# dsy01.net
KiCad netlist of a schematic drawn in EAGLE
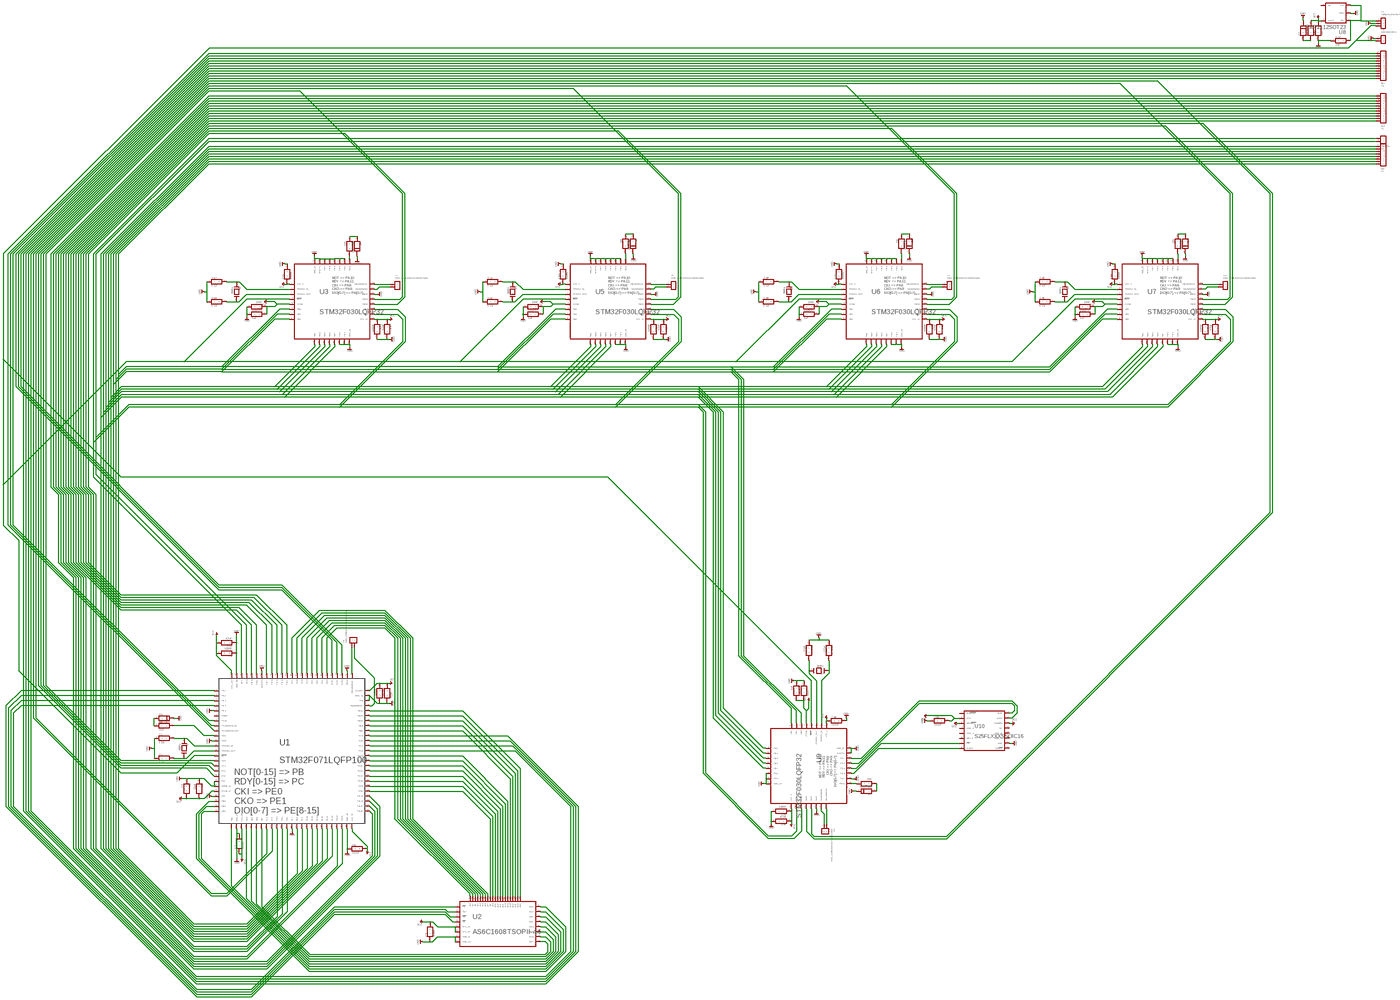
[diagram p0: schematic, sheet 1, overview]
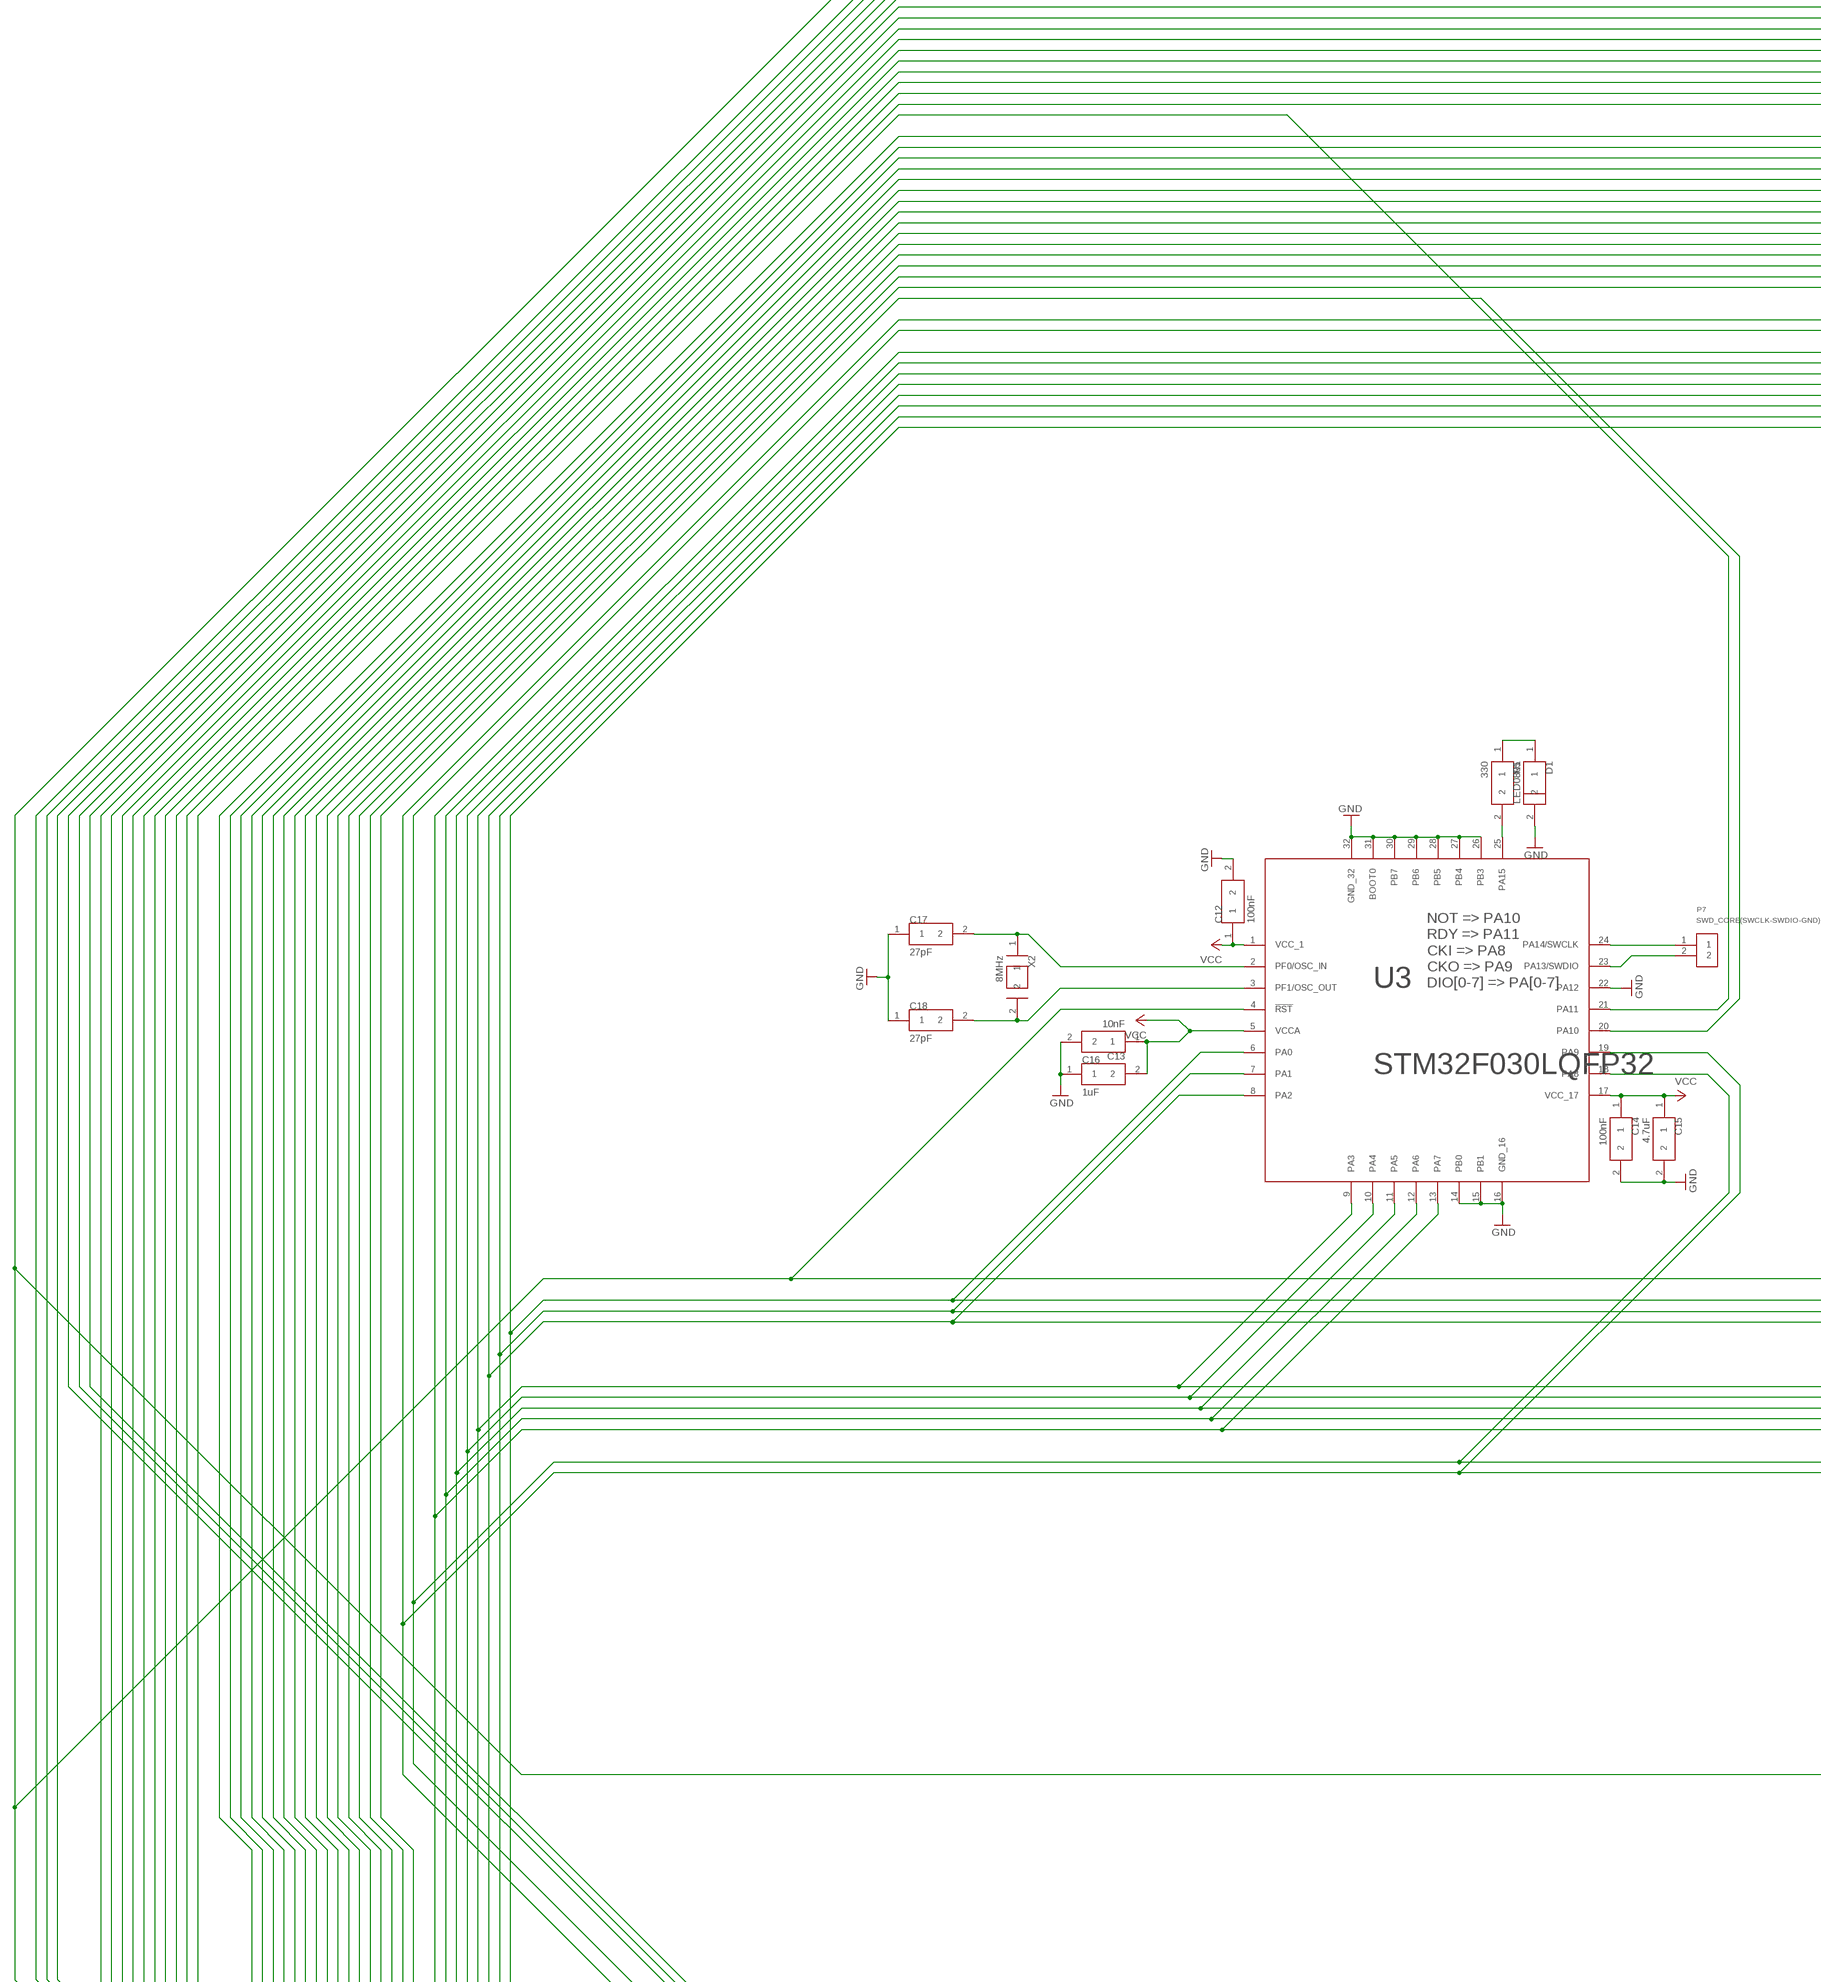
[diagram p1: schematic, sheet 1, part 1 of 7]
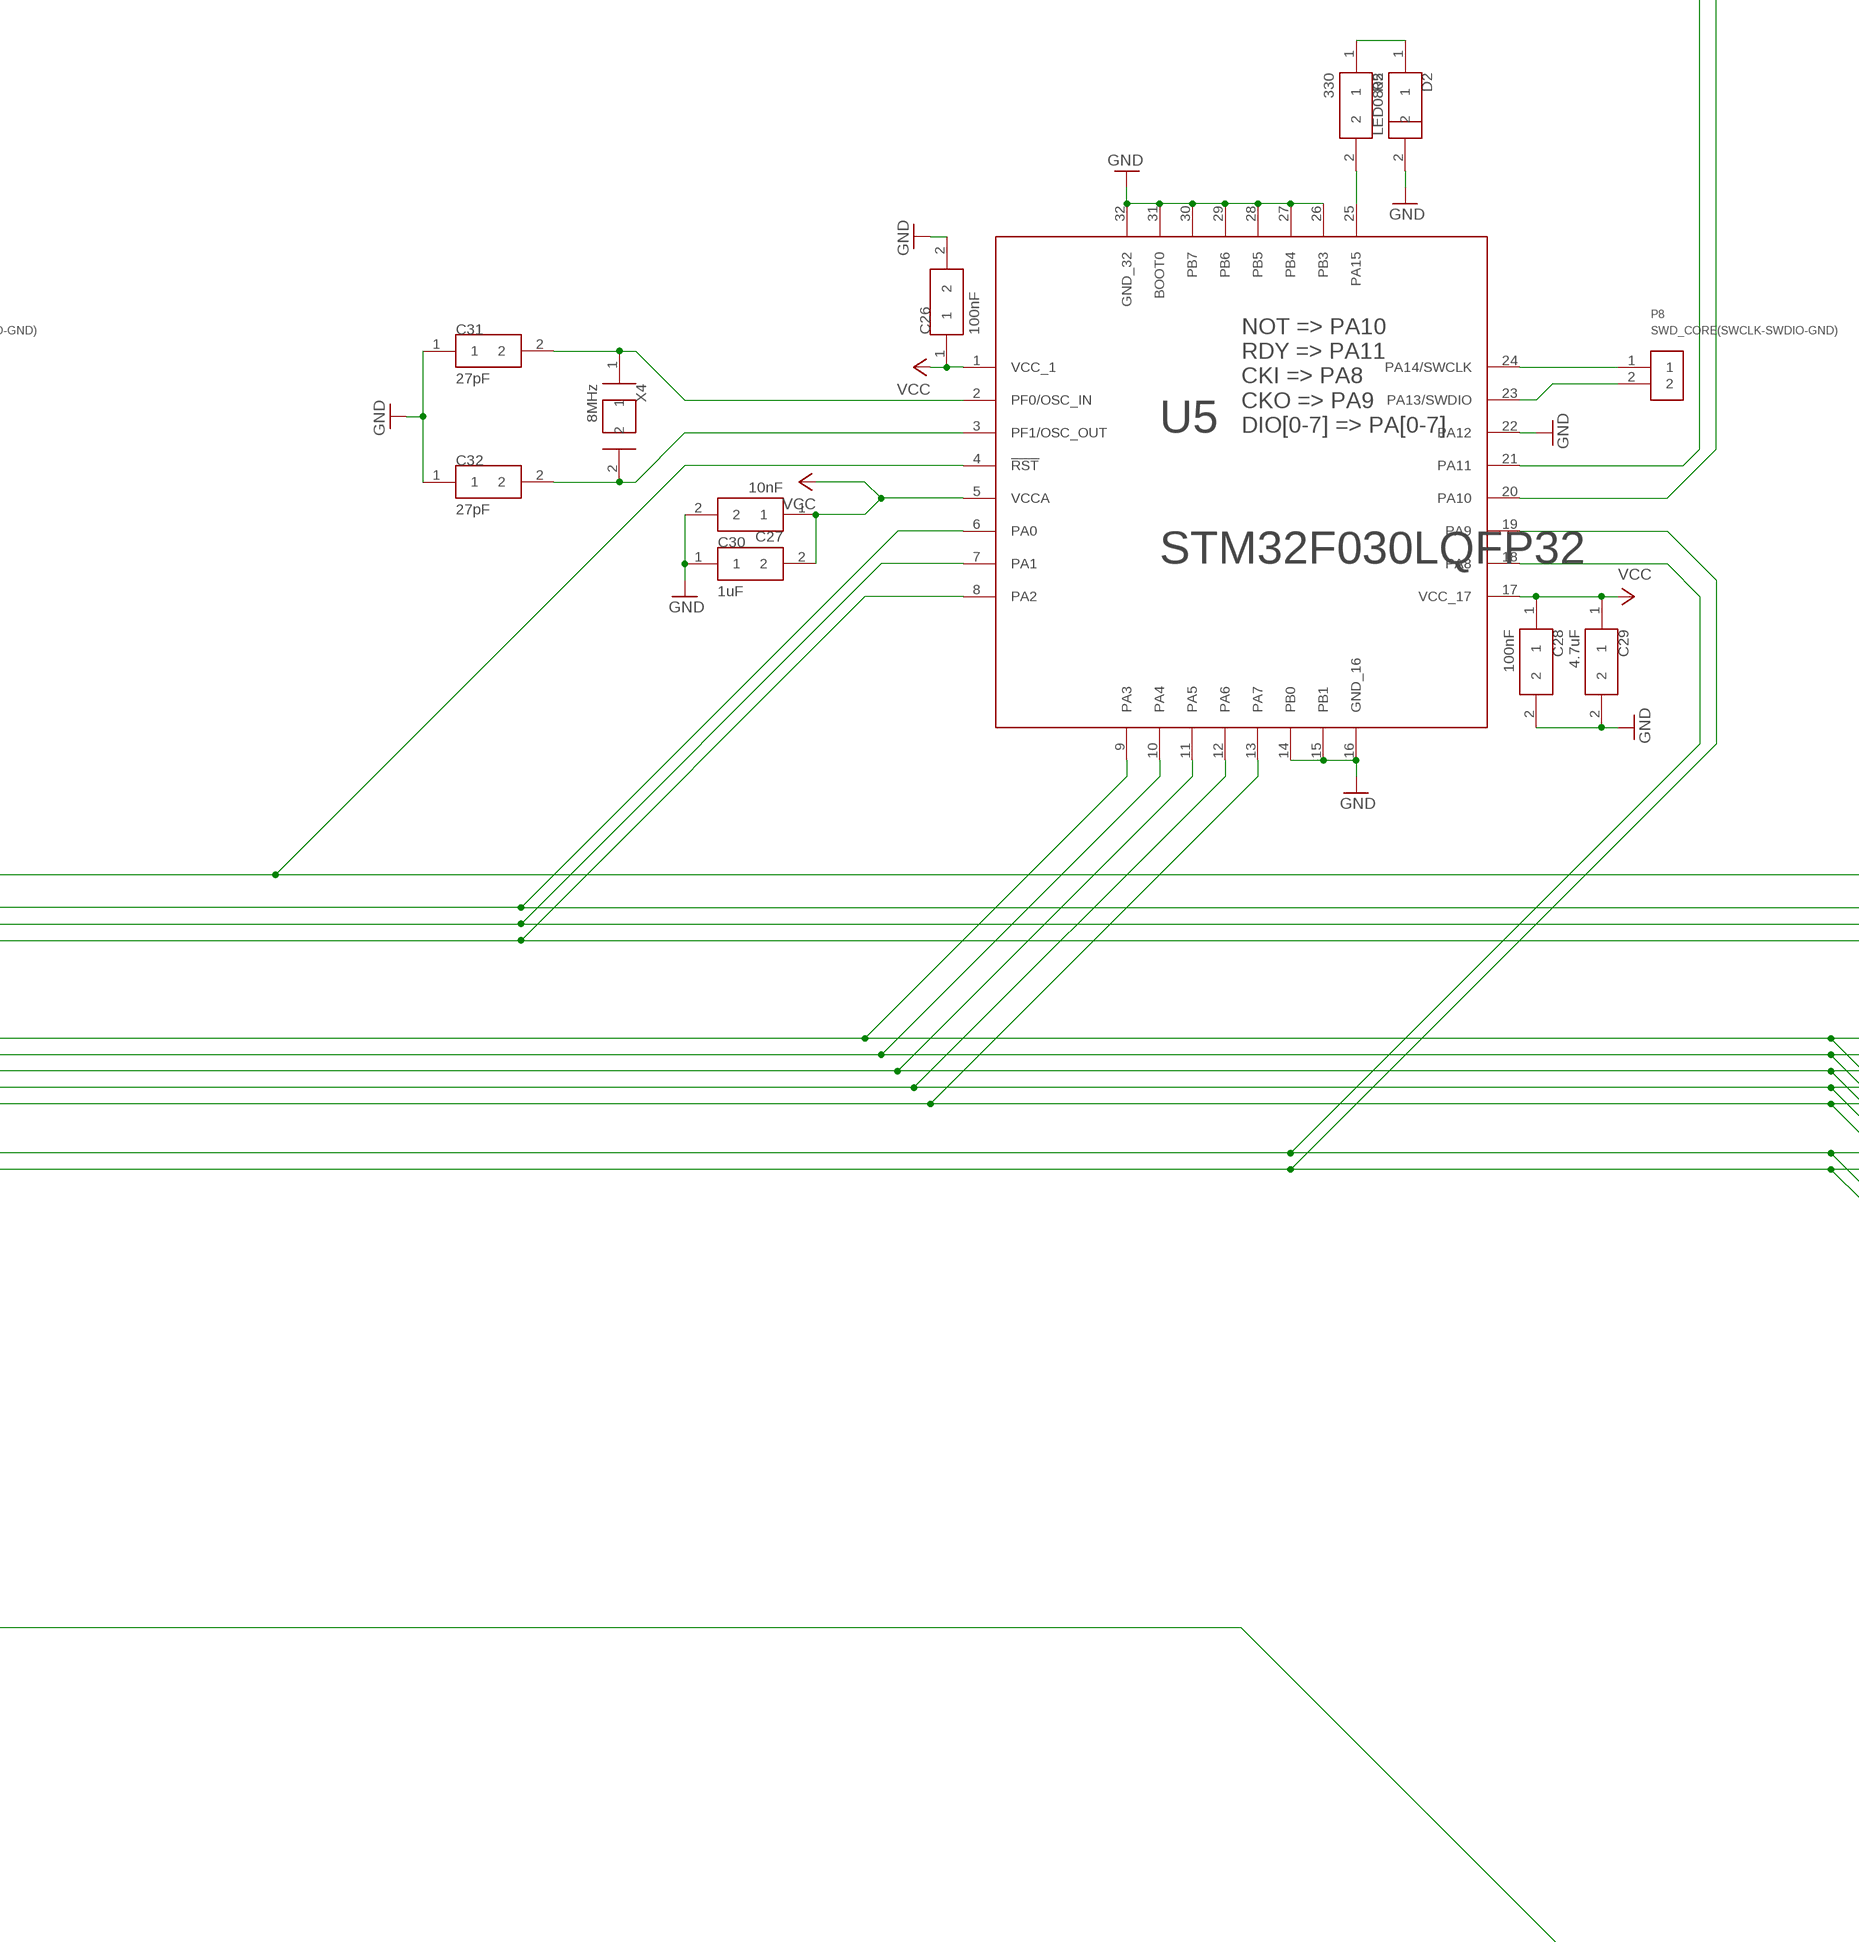
[diagram p2: schematic, sheet 1, part 2 of 7]
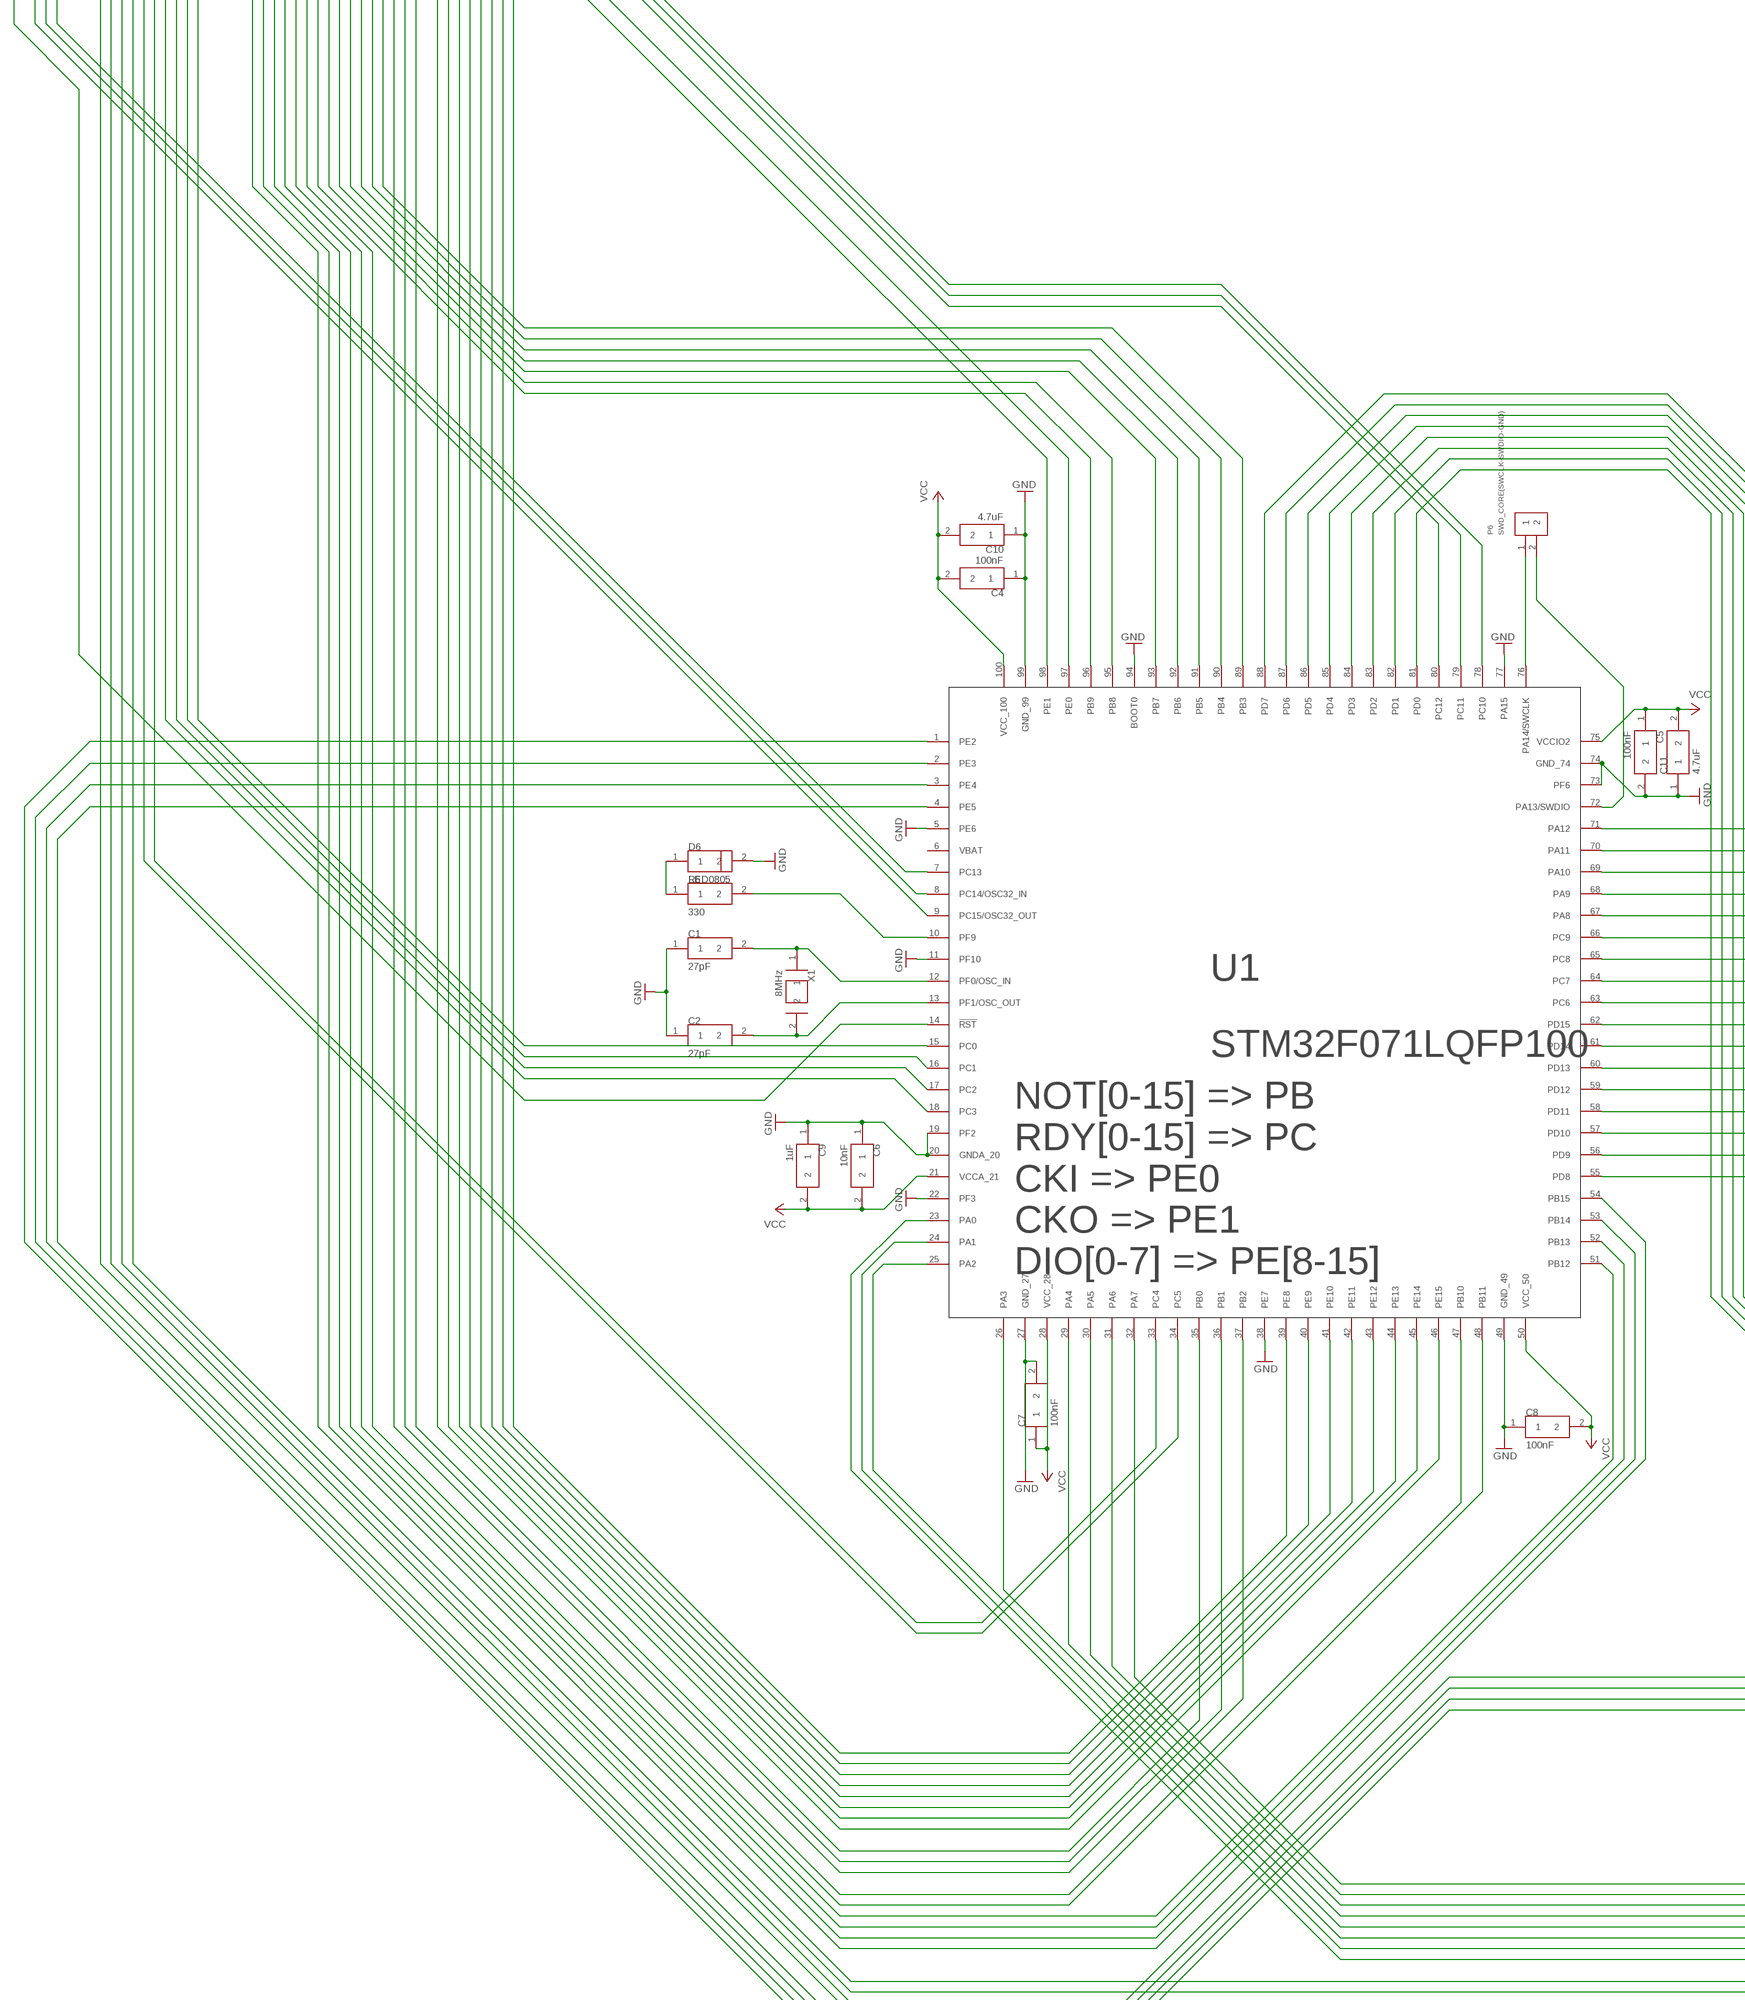
[diagram p3: schematic, sheet 1, part 3 of 7]
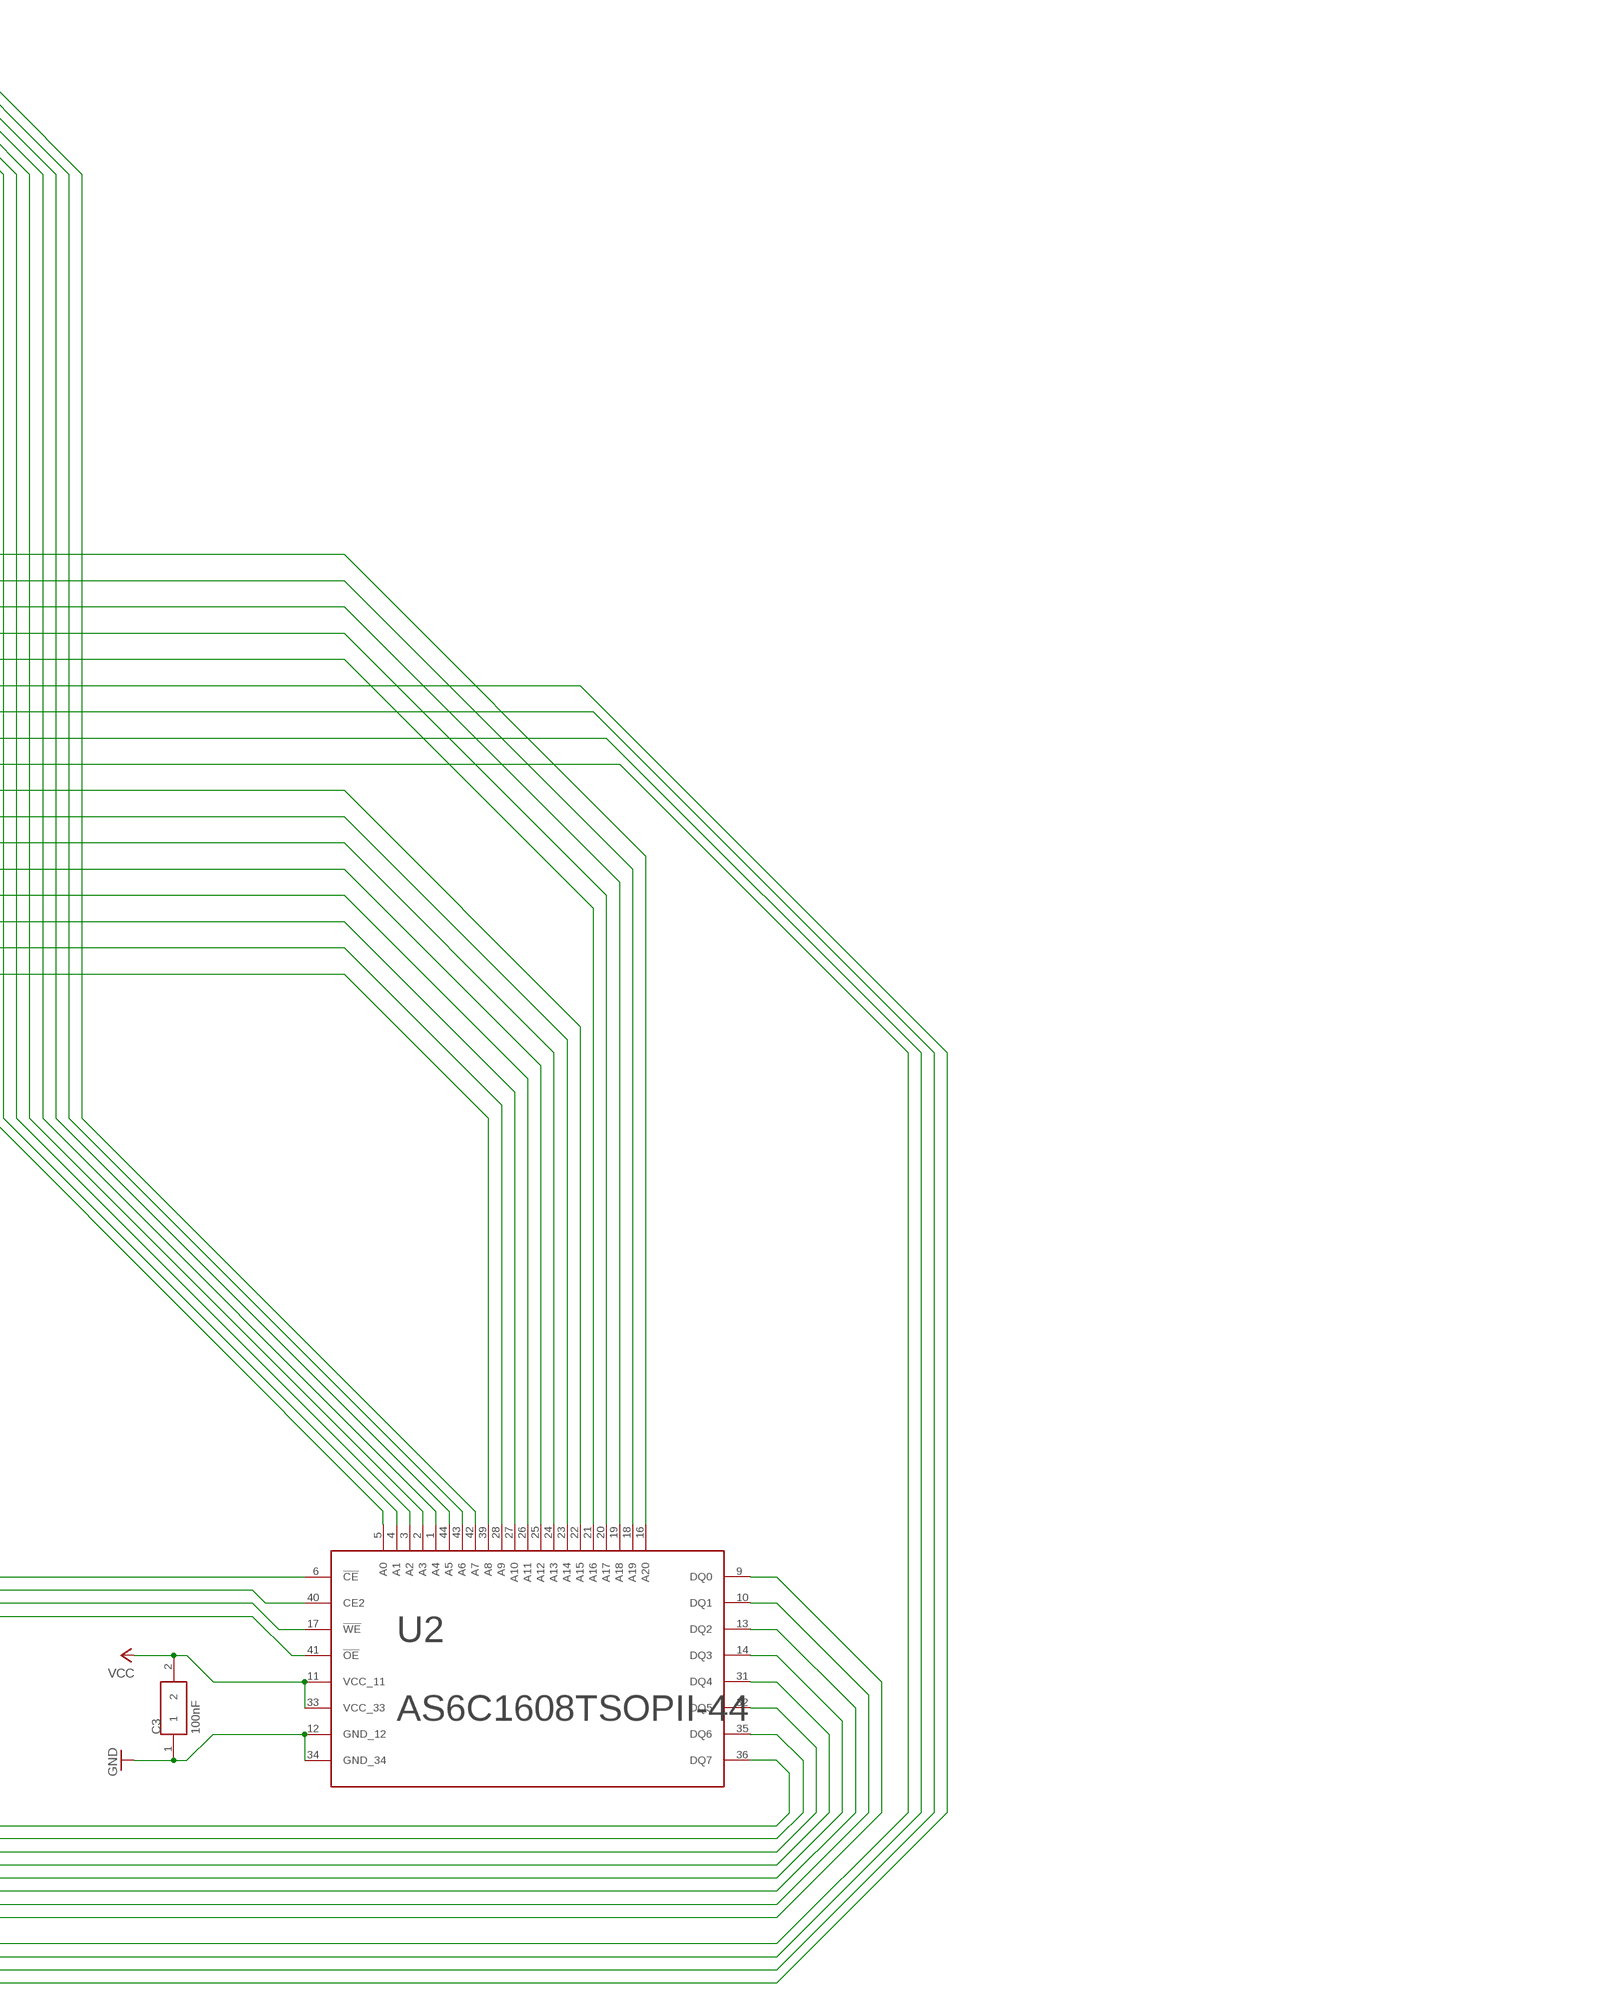
[diagram p4: schematic, sheet 1, part 4 of 7]
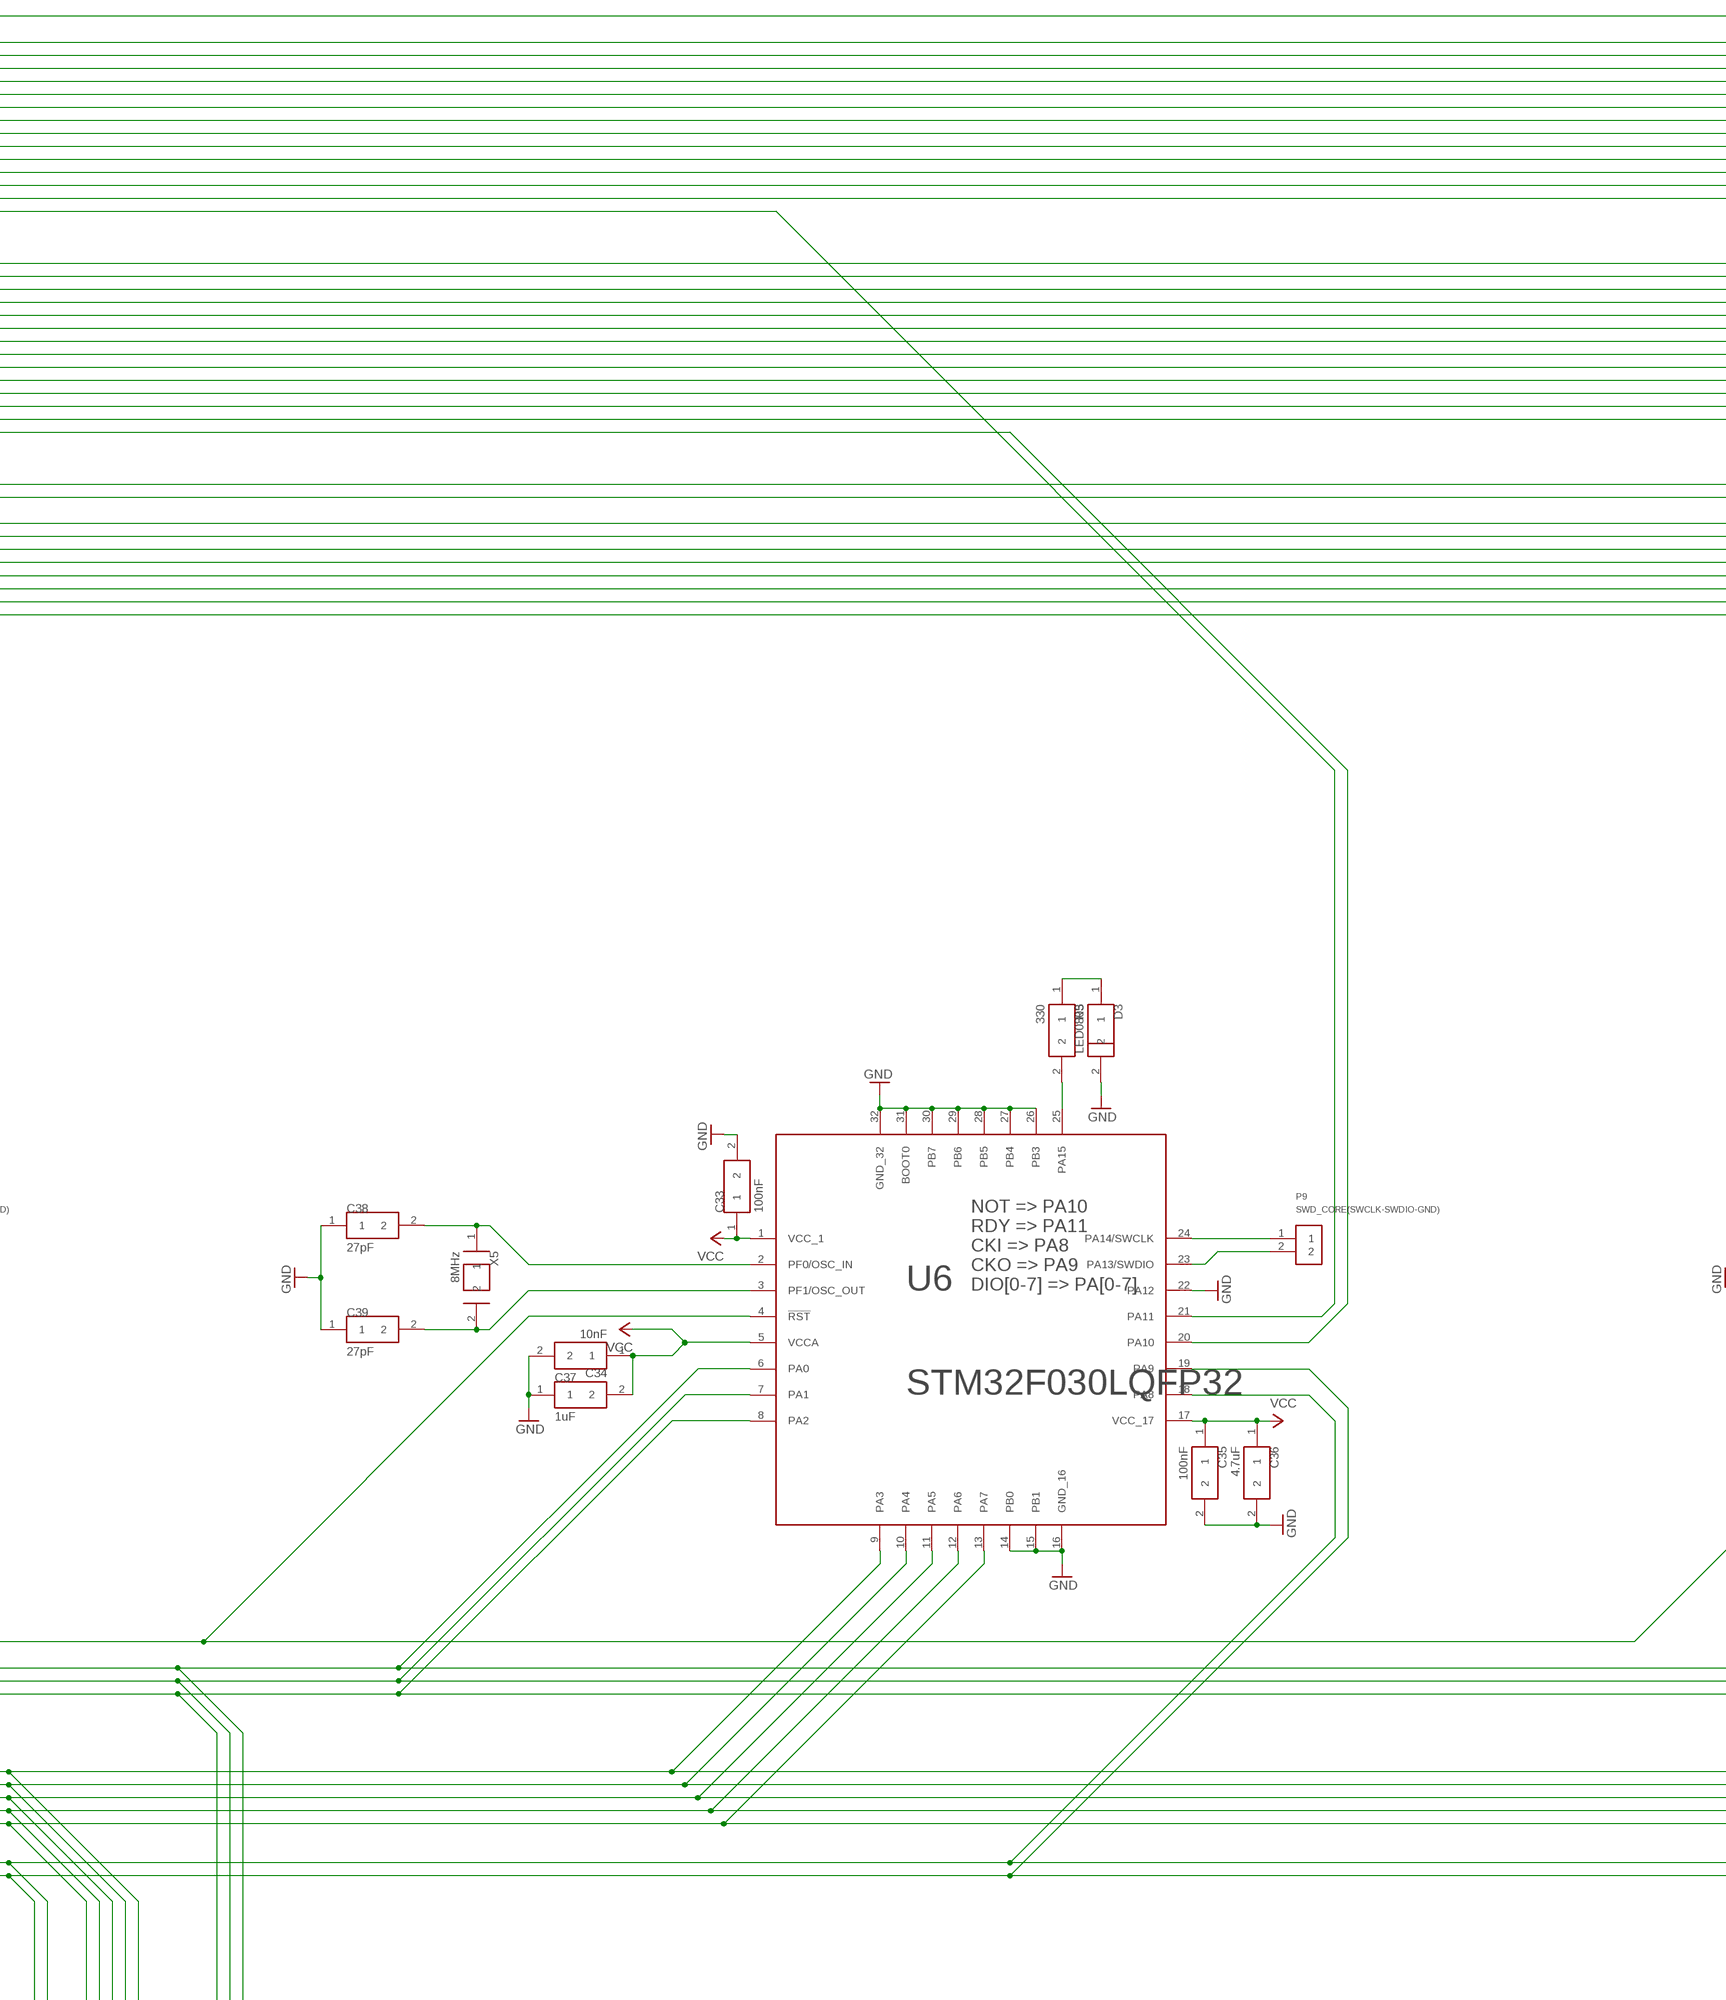
[diagram p5: schematic, sheet 1, part 5 of 7]
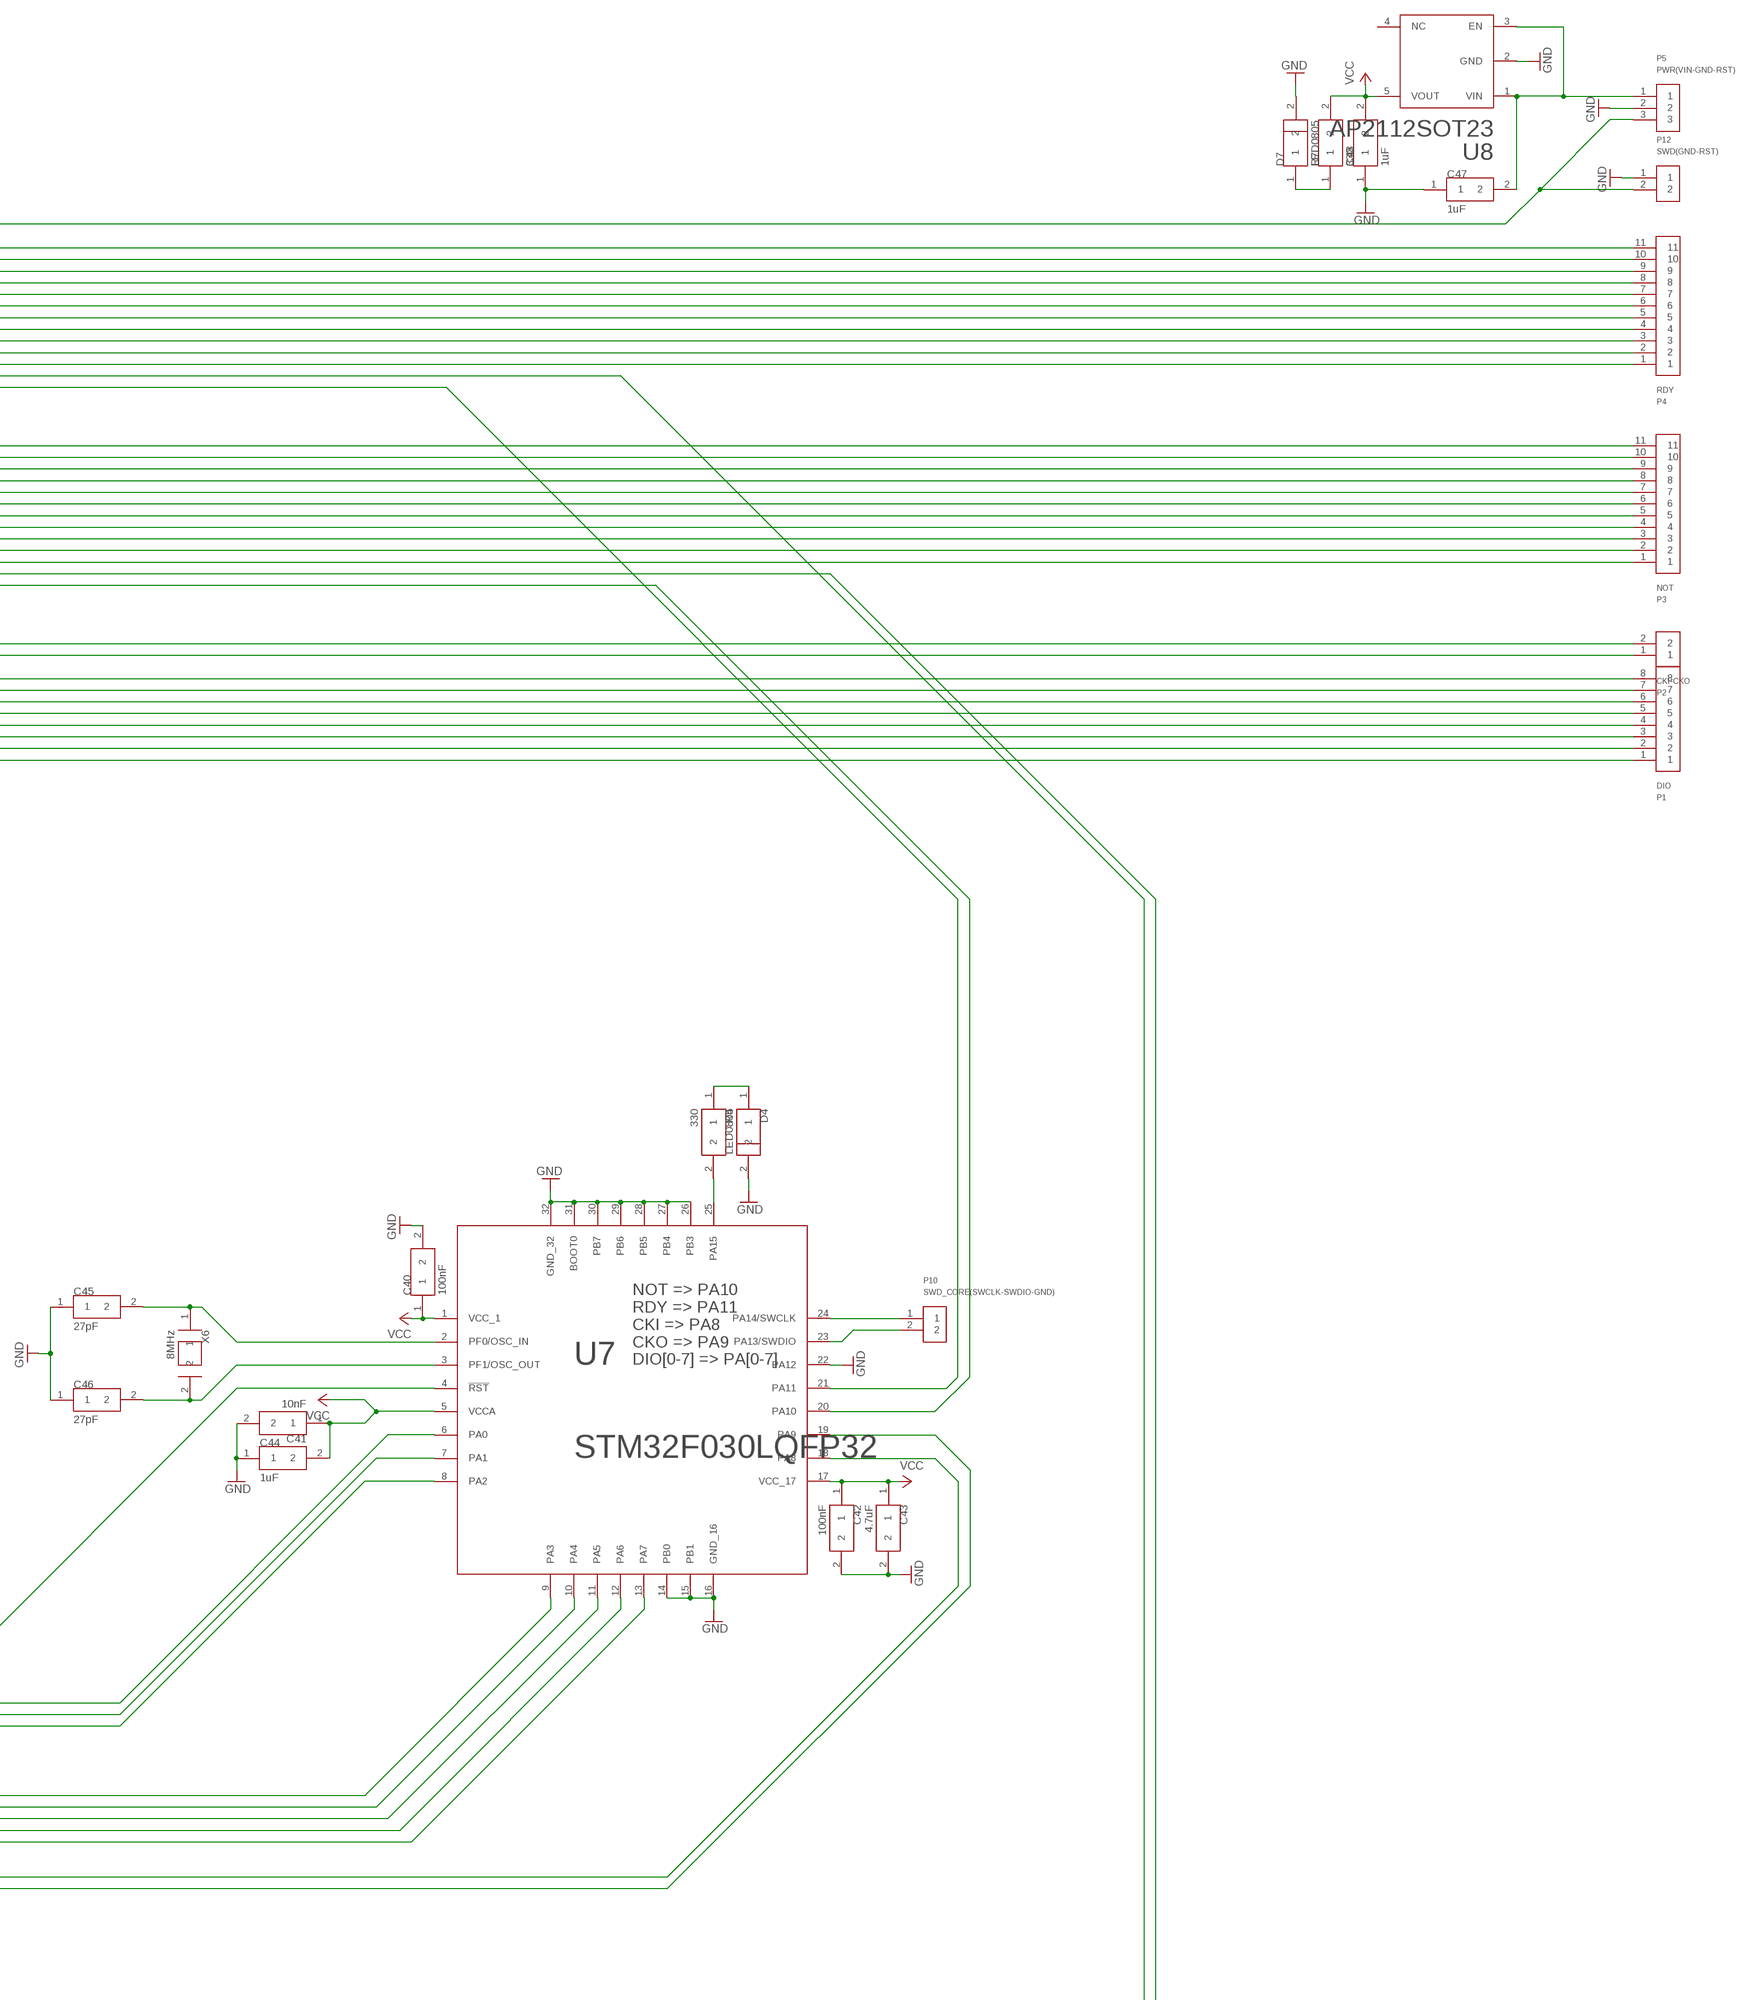
[diagram p6: schematic, sheet 1, part 6 of 7]
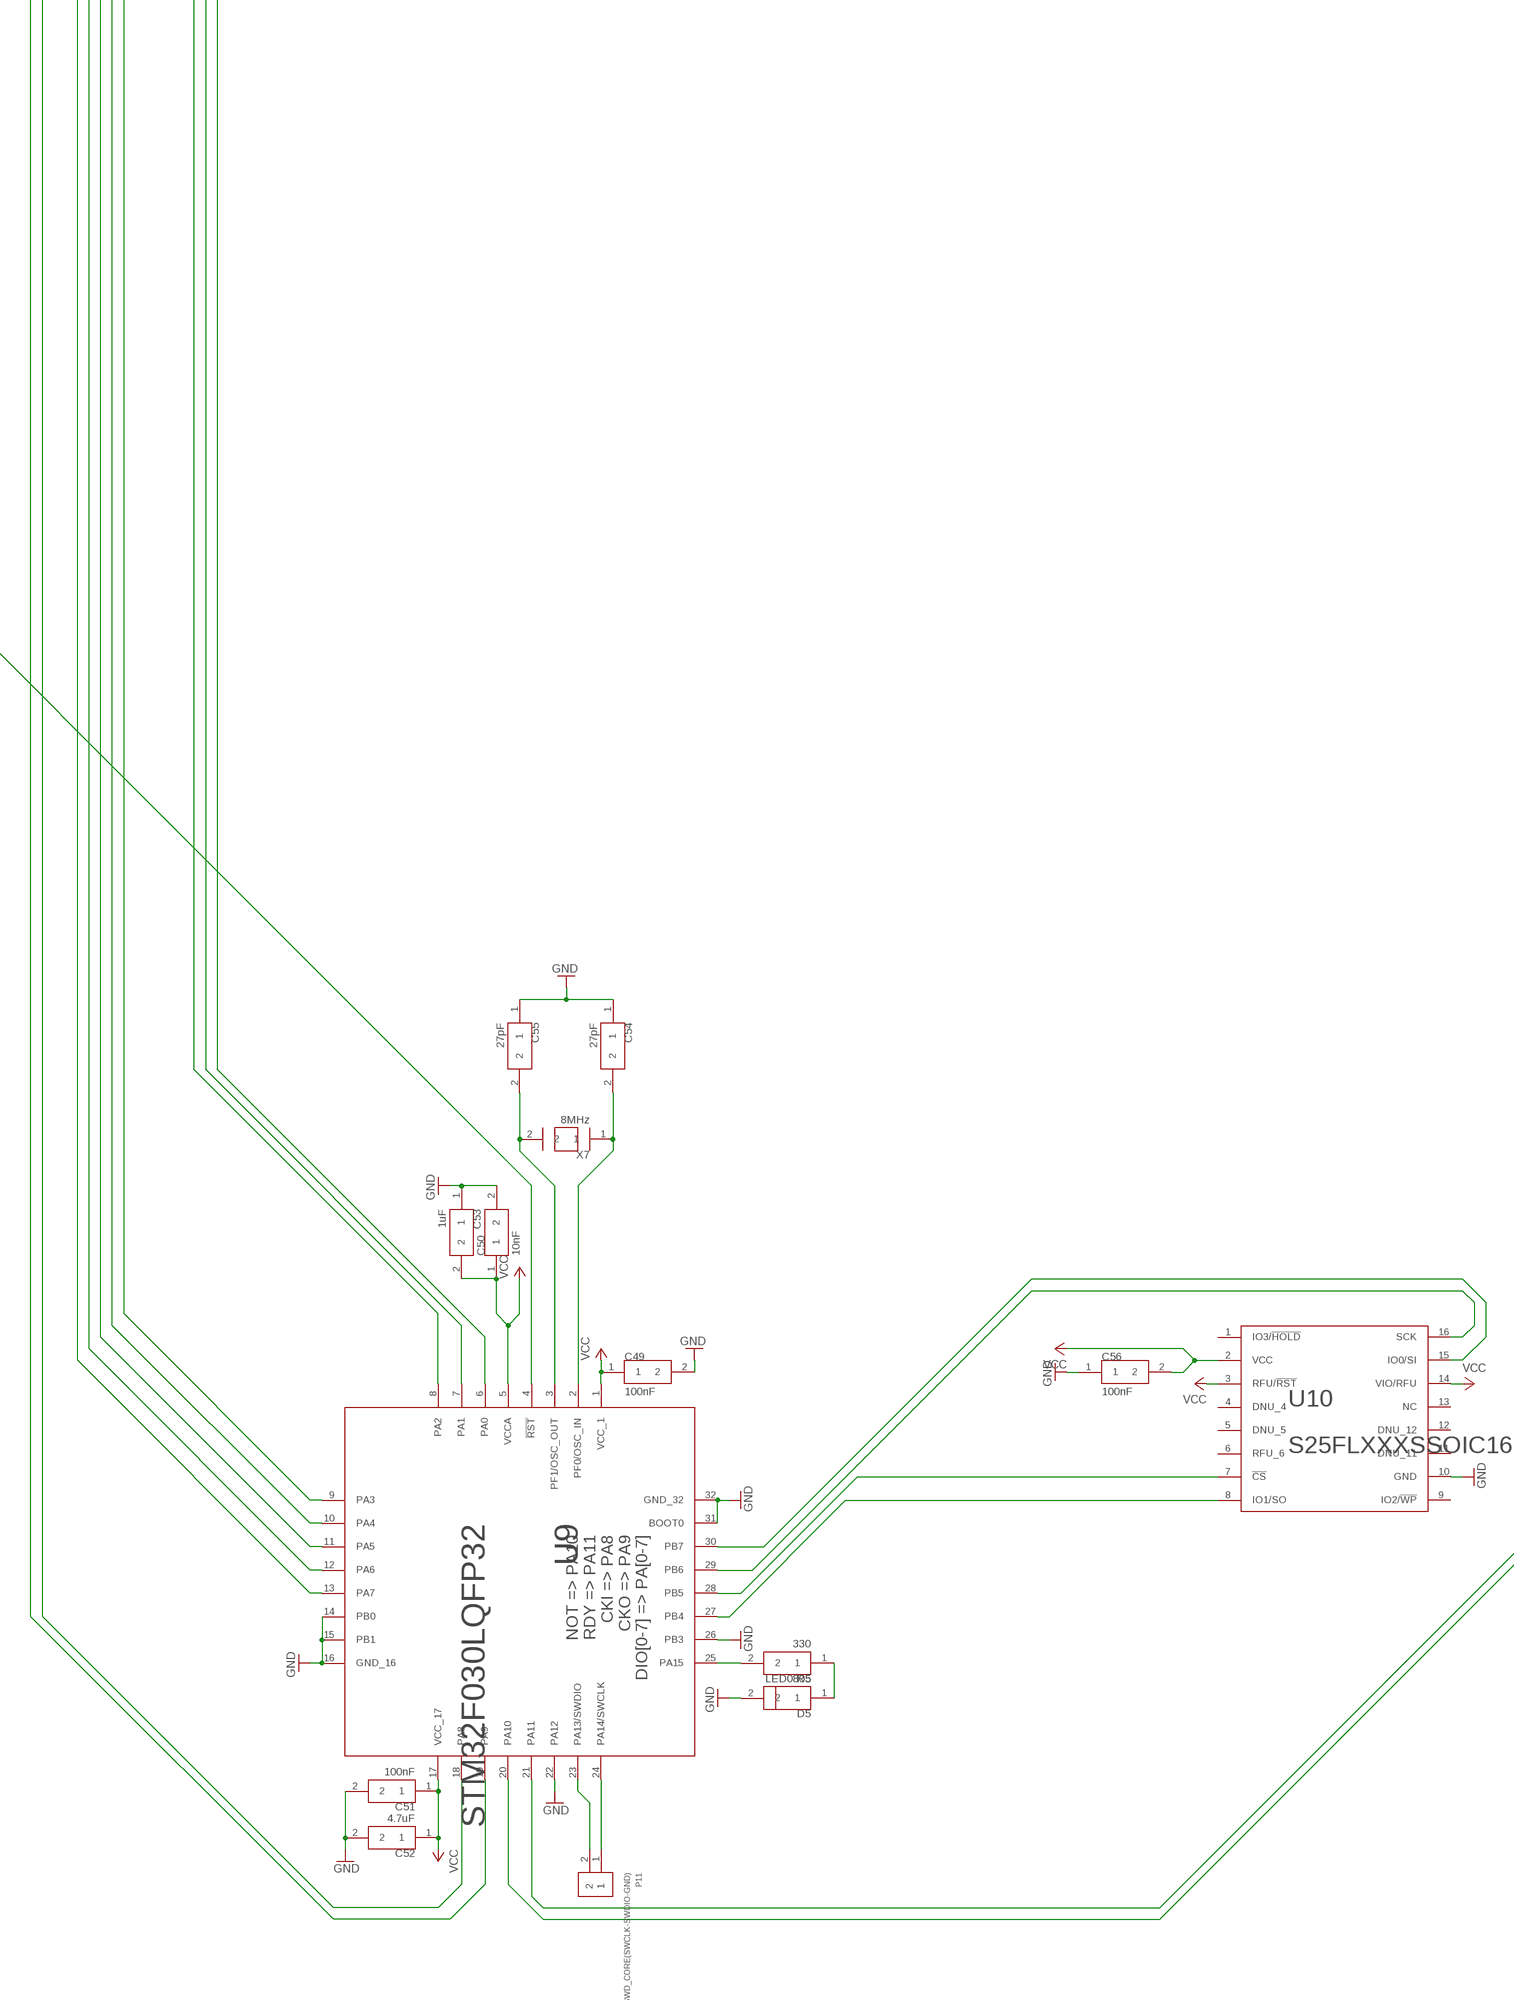
[diagram p7: schematic, sheet 1, part 7 of 7]

(export (version "E")
  (design (tool "Eeschema 10.0.6"))
  (components
    (comp (ref "C1")
      (value "27pF")
      (footprint "eagle-import:0805")
      (libsource (lib "eagle-import") (part "CAP0805"))
    )
    (comp (ref "C2")
      (value "27pF")
      (footprint "eagle-import:0805")
      (libsource (lib "eagle-import") (part "CAP0805"))
    )
    (comp (ref "C3")
      (value "100nF")
      (footprint "eagle-import:0805")
      (libsource (lib "eagle-import") (part "CAP0805"))
    )
    (comp (ref "C4")
      (value "100nF")
      (footprint "eagle-import:0805")
      (libsource (lib "eagle-import") (part "CAP0805"))
    )
    (comp (ref "C5")
      (value "100nF")
      (footprint "eagle-import:0805")
      (libsource (lib "eagle-import") (part "CAP0805"))
    )
    (comp (ref "C6")
      (value "10nF")
      (footprint "eagle-import:0805")
      (libsource (lib "eagle-import") (part "CAP0805"))
    )
    (comp (ref "C7")
      (value "100nF")
      (footprint "eagle-import:0805")
      (libsource (lib "eagle-import") (part "CAP0805"))
    )
    (comp (ref "C8")
      (value "100nF")
      (footprint "eagle-import:0805")
      (libsource (lib "eagle-import") (part "CAP0805"))
    )
    (comp (ref "C9")
      (value "1uF")
      (footprint "eagle-import:0805")
      (libsource (lib "eagle-import") (part "CAP0805"))
    )
    (comp (ref "C10")
      (value "4.7uF")
      (footprint "eagle-import:0805")
      (libsource (lib "eagle-import") (part "CAP0805"))
    )
    (comp (ref "C11")
      (value "4.7uF")
      (footprint "eagle-import:0805")
      (libsource (lib "eagle-import") (part "CAP0805"))
    )
    (comp (ref "C12")
      (value "100nF")
      (footprint "eagle-import:0805")
      (libsource (lib "eagle-import") (part "CAP0805"))
    )
    (comp (ref "C13")
      (value "10nF")
      (footprint "eagle-import:0805")
      (libsource (lib "eagle-import") (part "CAP0805"))
    )
    (comp (ref "C14")
      (value "100nF")
      (footprint "eagle-import:0805")
      (libsource (lib "eagle-import") (part "CAP0805"))
    )
    (comp (ref "C15")
      (value "4.7uF")
      (footprint "eagle-import:0805")
      (libsource (lib "eagle-import") (part "CAP0805"))
    )
    (comp (ref "C16")
      (value "1uF")
      (footprint "eagle-import:0805")
      (libsource (lib "eagle-import") (part "CAP0805"))
    )
    (comp (ref "C17")
      (value "27pF")
      (footprint "eagle-import:0805")
      (libsource (lib "eagle-import") (part "CAP0805"))
    )
    (comp (ref "C18")
      (value "27pF")
      (footprint "eagle-import:0805")
      (libsource (lib "eagle-import") (part "CAP0805"))
    )
    (comp (ref "C26")
      (value "100nF")
      (footprint "eagle-import:0805")
      (libsource (lib "eagle-import") (part "CAP0805"))
    )
    (comp (ref "C27")
      (value "10nF")
      (footprint "eagle-import:0805")
      (libsource (lib "eagle-import") (part "CAP0805"))
    )
    (comp (ref "C28")
      (value "100nF")
      (footprint "eagle-import:0805")
      (libsource (lib "eagle-import") (part "CAP0805"))
    )
    (comp (ref "C29")
      (value "4.7uF")
      (footprint "eagle-import:0805")
      (libsource (lib "eagle-import") (part "CAP0805"))
    )
    (comp (ref "C30")
      (value "1uF")
      (footprint "eagle-import:0805")
      (libsource (lib "eagle-import") (part "CAP0805"))
    )
    (comp (ref "C31")
      (value "27pF")
      (footprint "eagle-import:0805")
      (libsource (lib "eagle-import") (part "CAP0805"))
    )
    (comp (ref "C32")
      (value "27pF")
      (footprint "eagle-import:0805")
      (libsource (lib "eagle-import") (part "CAP0805"))
    )
    (comp (ref "C33")
      (value "100nF")
      (footprint "eagle-import:0805")
      (libsource (lib "eagle-import") (part "CAP0805"))
    )
    (comp (ref "C34")
      (value "10nF")
      (footprint "eagle-import:0805")
      (libsource (lib "eagle-import") (part "CAP0805"))
    )
    (comp (ref "C35")
      (value "100nF")
      (footprint "eagle-import:0805")
      (libsource (lib "eagle-import") (part "CAP0805"))
    )
    (comp (ref "C36")
      (value "4.7uF")
      (footprint "eagle-import:0805")
      (libsource (lib "eagle-import") (part "CAP0805"))
    )
    (comp (ref "C37")
      (value "1uF")
      (footprint "eagle-import:0805")
      (libsource (lib "eagle-import") (part "CAP0805"))
    )
    (comp (ref "C38")
      (value "27pF")
      (footprint "eagle-import:0805")
      (libsource (lib "eagle-import") (part "CAP0805"))
    )
    (comp (ref "C39")
      (value "27pF")
      (footprint "eagle-import:0805")
      (libsource (lib "eagle-import") (part "CAP0805"))
    )
    (comp (ref "C40")
      (value "100nF")
      (footprint "eagle-import:0805")
      (libsource (lib "eagle-import") (part "CAP0805"))
    )
    (comp (ref "C41")
      (value "10nF")
      (footprint "eagle-import:0805")
      (libsource (lib "eagle-import") (part "CAP0805"))
    )
    (comp (ref "C42")
      (value "100nF")
      (footprint "eagle-import:0805")
      (libsource (lib "eagle-import") (part "CAP0805"))
    )
    (comp (ref "C43")
      (value "4.7uF")
      (footprint "eagle-import:0805")
      (libsource (lib "eagle-import") (part "CAP0805"))
    )
    (comp (ref "C44")
      (value "1uF")
      (footprint "eagle-import:0805")
      (libsource (lib "eagle-import") (part "CAP0805"))
    )
    (comp (ref "C45")
      (value "27pF")
      (footprint "eagle-import:0805")
      (libsource (lib "eagle-import") (part "CAP0805"))
    )
    (comp (ref "C46")
      (value "27pF")
      (footprint "eagle-import:0805")
      (libsource (lib "eagle-import") (part "CAP0805"))
    )
    (comp (ref "C47")
      (value "1uF")
      (footprint "eagle-import:0805")
      (libsource (lib "eagle-import") (part "CAP0805"))
    )
    (comp (ref "C48")
      (value "1uF")
      (footprint "eagle-import:0805")
      (libsource (lib "eagle-import") (part "CAP0805"))
    )
    (comp (ref "C49")
      (value "100nF")
      (footprint "eagle-import:0805")
      (libsource (lib "eagle-import") (part "CAP0805"))
    )
    (comp (ref "C50")
      (value "10nF")
      (footprint "eagle-import:0805")
      (libsource (lib "eagle-import") (part "CAP0805"))
    )
    (comp (ref "C51")
      (value "100nF")
      (footprint "eagle-import:0805")
      (libsource (lib "eagle-import") (part "CAP0805"))
    )
    (comp (ref "C52")
      (value "4.7uF")
      (footprint "eagle-import:0805")
      (libsource (lib "eagle-import") (part "CAP0805"))
    )
    (comp (ref "C53")
      (value "1uF")
      (footprint "eagle-import:0805")
      (libsource (lib "eagle-import") (part "CAP0805"))
    )
    (comp (ref "C54")
      (value "27pF")
      (footprint "eagle-import:0805")
      (libsource (lib "eagle-import") (part "CAP0805"))
    )
    (comp (ref "C55")
      (value "27pF")
      (footprint "eagle-import:0805")
      (libsource (lib "eagle-import") (part "CAP0805"))
    )
    (comp (ref "C56")
      (value "100nF")
      (footprint "eagle-import:0805")
      (libsource (lib "eagle-import") (part "CAP0805"))
    )
    (comp (ref "D1")
      (value "LED0805")
      (footprint "eagle-import:0805")
      (libsource (lib "eagle-import") (part "LED0805"))
    )
    (comp (ref "D2")
      (value "LED0805")
      (footprint "eagle-import:0805")
      (libsource (lib "eagle-import") (part "LED0805"))
    )
    (comp (ref "D3")
      (value "LED0805")
      (footprint "eagle-import:0805")
      (libsource (lib "eagle-import") (part "LED0805"))
    )
    (comp (ref "D4")
      (value "LED0805")
      (footprint "eagle-import:0805")
      (libsource (lib "eagle-import") (part "LED0805"))
    )
    (comp (ref "D5")
      (value "LED0805")
      (footprint "eagle-import:0805")
      (libsource (lib "eagle-import") (part "LED0805"))
    )
    (comp (ref "D6")
      (value "LED0805")
      (footprint "eagle-import:0805")
      (libsource (lib "eagle-import") (part "LED0805"))
    )
    (comp (ref "D7")
      (value "LED0805")
      (footprint "eagle-import:0805")
      (libsource (lib "eagle-import") (part "LED0805"))
    )
    (comp (ref "P1")
      (value "DIO")
      (footprint "eagle-import:PIN_8")
      (libsource (lib "eagle-import") (part "PIN_8"))
    )
    (comp (ref "P2")
      (value "CKI-CKO")
      (footprint "eagle-import:PIN_2")
      (libsource (lib "eagle-import") (part "PIN_2"))
    )
    (comp (ref "P3")
      (value "NOT")
      (footprint "eagle-import:PIN_11")
      (libsource (lib "eagle-import") (part "PIN_11"))
    )
    (comp (ref "P4")
      (value "RDY")
      (footprint "eagle-import:PIN_11")
      (libsource (lib "eagle-import") (part "PIN_11"))
    )
    (comp (ref "P5")
      (value "PWR(VIN-GND-RST)")
      (footprint "eagle-import:PIN_3")
      (libsource (lib "eagle-import") (part "PIN_3"))
    )
    (comp (ref "P6")
      (value "SWD_CORE(SWCLK-SWDIO-GND)")
      (footprint "eagle-import:PIN_2")
      (libsource (lib "eagle-import") (part "PIN_2"))
    )
    (comp (ref "P7")
      (value "SWD_CORE(SWCLK-SWDIO-GND)")
      (footprint "eagle-import:PIN_2")
      (libsource (lib "eagle-import") (part "PIN_2"))
    )
    (comp (ref "P8")
      (value "SWD_CORE(SWCLK-SWDIO-GND)")
      (footprint "eagle-import:PIN_2")
      (libsource (lib "eagle-import") (part "PIN_2"))
    )
    (comp (ref "P9")
      (value "SWD_CORE(SWCLK-SWDIO-GND)")
      (footprint "eagle-import:PIN_2")
      (libsource (lib "eagle-import") (part "PIN_2"))
    )
    (comp (ref "P10")
      (value "SWD_CORE(SWCLK-SWDIO-GND)")
      (footprint "eagle-import:PIN_2")
      (libsource (lib "eagle-import") (part "PIN_2"))
    )
    (comp (ref "P11")
      (value "SWD_CORE(SWCLK-SWDIO-GND)")
      (footprint "eagle-import:PIN_2")
      (libsource (lib "eagle-import") (part "PIN_2"))
    )
    (comp (ref "P12")
      (value "SWD(GND-RST)")
      (footprint "eagle-import:PIN_2")
      (libsource (lib "eagle-import") (part "PIN_2"))
    )
    (comp (ref "R1")
      (value "330")
      (footprint "eagle-import:0805")
      (libsource (lib "eagle-import") (part "RES0805"))
    )
    (comp (ref "R2")
      (value "330")
      (footprint "eagle-import:0805")
      (libsource (lib "eagle-import") (part "RES0805"))
    )
    (comp (ref "R3")
      (value "330")
      (footprint "eagle-import:0805")
      (libsource (lib "eagle-import") (part "RES0805"))
    )
    (comp (ref "R4")
      (value "330")
      (footprint "eagle-import:0805")
      (libsource (lib "eagle-import") (part "RES0805"))
    )
    (comp (ref "R5")
      (value "330")
      (footprint "eagle-import:0805")
      (libsource (lib "eagle-import") (part "RES0805"))
    )
    (comp (ref "R6")
      (value "330")
      (footprint "eagle-import:0805")
      (libsource (lib "eagle-import") (part "RES0805"))
    )
    (comp (ref "R7")
      (value "330")
      (footprint "eagle-import:0805")
      (libsource (lib "eagle-import") (part "RES0805"))
    )
    (comp (ref "U1")
      (value "STM32F071LQFP100")
      (footprint "eagle-import:QFP100")
      (libsource (lib "eagle-import") (part "STM32F071LQFP100"))
    )
    (comp (ref "U2")
      (value "AS6C1608TSOPII-44")
      (footprint "eagle-import:TSOPII-44")
      (libsource (lib "eagle-import") (part "AS6C1608TSOPII-44"))
    )
    (comp (ref "U3")
      (value "STM32F030LQFP32")
      (footprint "eagle-import:QFP32")
      (libsource (lib "eagle-import") (part "STM32F030LQFP32"))
    )
    (comp (ref "U5")
      (value "STM32F030LQFP32")
      (footprint "eagle-import:QFP32")
      (libsource (lib "eagle-import") (part "STM32F030LQFP32"))
    )
    (comp (ref "U6")
      (value "STM32F030LQFP32")
      (footprint "eagle-import:QFP32")
      (libsource (lib "eagle-import") (part "STM32F030LQFP32"))
    )
    (comp (ref "U7")
      (value "STM32F030LQFP32")
      (footprint "eagle-import:QFP32")
      (libsource (lib "eagle-import") (part "STM32F030LQFP32"))
    )
    (comp (ref "U8")
      (value "AP2112SOT23")
      (footprint "eagle-import:SOT23-5")
      (libsource (lib "eagle-import") (part "AP2112SOT23"))
    )
    (comp (ref "U9")
      (value "STM32F030LQFP32")
      (footprint "eagle-import:QFP32")
      (libsource (lib "eagle-import") (part "STM32F030LQFP32"))
    )
    (comp (ref "U10")
      (value "S25FLXXXSSOIC16")
      (footprint "eagle-import:SO3-016")
      (libsource (lib "eagle-import") (part "S25FLXXXSSOIC16"))
    )
    (comp (ref "X1")
      (value "8MHz")
      (footprint "eagle-import:XTAL_532")
      (libsource (lib "eagle-import") (part "XTALSMD-5X32"))
    )
    (comp (ref "X2")
      (value "8MHz")
      (footprint "eagle-import:XTAL_532")
      (libsource (lib "eagle-import") (part "XTALSMD-5X32"))
    )
    (comp (ref "X4")
      (value "8MHz")
      (footprint "eagle-import:XTAL_532")
      (libsource (lib "eagle-import") (part "XTALSMD-5X32"))
    )
    (comp (ref "X5")
      (value "8MHz")
      (footprint "eagle-import:XTAL_532")
      (libsource (lib "eagle-import") (part "XTALSMD-5X32"))
    )
    (comp (ref "X6")
      (value "8MHz")
      (footprint "eagle-import:XTAL_532")
      (libsource (lib "eagle-import") (part "XTALSMD-5X32"))
    )
    (comp (ref "X7")
      (value "8MHz")
      (footprint "eagle-import:XTAL_532")
      (libsource (lib "eagle-import") (part "XTALSMD-5X32"))
    )
  )
  (nets
    (net (code "1") (name "GND") (class "Default")
      (node (ref "C1") (pin "1") (pinfunction "1_1") (pintype "bidirectional"))
      (node (ref "C10") (pin "1") (pinfunction "1_1") (pintype "bidirectional"))
      (node (ref "C11") (pin "1") (pinfunction "1_1") (pintype "bidirectional"))
      (node (ref "C12") (pin "2") (pinfunction "2_2") (pintype "bidirectional"))
      (node (ref "C13") (pin "2") (pinfunction "2_2") (pintype "bidirectional"))
      (node (ref "C14") (pin "2") (pinfunction "2_2") (pintype "bidirectional"))
      (node (ref "C15") (pin "2") (pinfunction "2_2") (pintype "bidirectional"))
      (node (ref "C16") (pin "1") (pinfunction "1_1") (pintype "bidirectional"))
      (node (ref "C17") (pin "1") (pinfunction "1_1") (pintype "bidirectional"))
      (node (ref "C18") (pin "1") (pinfunction "1_1") (pintype "bidirectional"))
      (node (ref "C2") (pin "1") (pinfunction "1_1") (pintype "bidirectional"))
      (node (ref "C26") (pin "2") (pinfunction "2_2") (pintype "bidirectional"))
      (node (ref "C27") (pin "2") (pinfunction "2_2") (pintype "bidirectional"))
      (node (ref "C28") (pin "2") (pinfunction "2_2") (pintype "bidirectional"))
      (node (ref "C29") (pin "2") (pinfunction "2_2") (pintype "bidirectional"))
      (node (ref "C3") (pin "1") (pinfunction "1_1") (pintype "bidirectional"))
      (node (ref "C30") (pin "1") (pinfunction "1_1") (pintype "bidirectional"))
      (node (ref "C31") (pin "1") (pinfunction "1_1") (pintype "bidirectional"))
      (node (ref "C32") (pin "1") (pinfunction "1_1") (pintype "bidirectional"))
      (node (ref "C33") (pin "2") (pinfunction "2_2") (pintype "bidirectional"))
      (node (ref "C34") (pin "2") (pinfunction "2_2") (pintype "bidirectional"))
      (node (ref "C35") (pin "2") (pinfunction "2_2") (pintype "bidirectional"))
      (node (ref "C36") (pin "2") (pinfunction "2_2") (pintype "bidirectional"))
      (node (ref "C37") (pin "1") (pinfunction "1_1") (pintype "bidirectional"))
      (node (ref "C38") (pin "1") (pinfunction "1_1") (pintype "bidirectional"))
      (node (ref "C39") (pin "1") (pinfunction "1_1") (pintype "bidirectional"))
      (node (ref "C4") (pin "1") (pinfunction "1_1") (pintype "bidirectional"))
      (node (ref "C40") (pin "2") (pinfunction "2_2") (pintype "bidirectional"))
      (node (ref "C41") (pin "2") (pinfunction "2_2") (pintype "bidirectional"))
      (node (ref "C42") (pin "2") (pinfunction "2_2") (pintype "bidirectional"))
      (node (ref "C43") (pin "2") (pinfunction "2_2") (pintype "bidirectional"))
      (node (ref "C44") (pin "1") (pinfunction "1_1") (pintype "bidirectional"))
      (node (ref "C45") (pin "1") (pinfunction "1_1") (pintype "bidirectional"))
      (node (ref "C46") (pin "1") (pinfunction "1_1") (pintype "bidirectional"))
      (node (ref "C47") (pin "1") (pinfunction "1_1") (pintype "bidirectional"))
      (node (ref "C48") (pin "1") (pinfunction "1_1") (pintype "bidirectional"))
      (node (ref "C49") (pin "2") (pinfunction "2_2") (pintype "bidirectional"))
      (node (ref "C5") (pin "2") (pinfunction "2_2") (pintype "bidirectional"))
      (node (ref "C50") (pin "2") (pinfunction "2_2") (pintype "bidirectional"))
      (node (ref "C51") (pin "2") (pinfunction "2_2") (pintype "bidirectional"))
      (node (ref "C52") (pin "2") (pinfunction "2_2") (pintype "bidirectional"))
      (node (ref "C53") (pin "1") (pinfunction "1_1") (pintype "bidirectional"))
      (node (ref "C54") (pin "1") (pinfunction "1_1") (pintype "bidirectional"))
      (node (ref "C55") (pin "1") (pinfunction "1_1") (pintype "bidirectional"))
      (node (ref "C56") (pin "1") (pinfunction "1_1") (pintype "bidirectional"))
      (node (ref "C6") (pin "1") (pinfunction "1_1") (pintype "bidirectional"))
      (node (ref "C7") (pin "2") (pinfunction "2_2") (pintype "bidirectional"))
      (node (ref "C8") (pin "1") (pinfunction "1_1") (pintype "bidirectional"))
      (node (ref "C9") (pin "1") (pinfunction "1_1") (pintype "bidirectional"))
      (node (ref "D1") (pin "2") (pinfunction "2_2") (pintype "bidirectional"))
      (node (ref "D2") (pin "2") (pinfunction "2_2") (pintype "bidirectional"))
      (node (ref "D3") (pin "2") (pinfunction "2_2") (pintype "bidirectional"))
      (node (ref "D4") (pin "2") (pinfunction "2_2") (pintype "bidirectional"))
      (node (ref "D5") (pin "2") (pinfunction "2_2") (pintype "bidirectional"))
      (node (ref "D6") (pin "2") (pinfunction "2_2") (pintype "bidirectional"))
      (node (ref "D7") (pin "2") (pinfunction "2_2") (pintype "bidirectional"))
      (node (ref "P12") (pin "1") (pinfunction "1_1") (pintype "bidirectional"))
      (node (ref "P5") (pin "2") (pinfunction "2_2") (pintype "bidirectional"))
      (node (ref "U1") (pin "11") (pinfunction "PF10_11") (pintype "bidirectional"))
      (node (ref "U1") (pin "19") (pinfunction "PF2_19") (pintype "bidirectional"))
      (node (ref "U1") (pin "20") (pinfunction "GNDA_20_20") (pintype "bidirectional"))
      (node (ref "U1") (pin "22") (pinfunction "PF3_22") (pintype "bidirectional"))
      (node (ref "U1") (pin "27") (pinfunction "GND_27_27") (pintype "bidirectional"))
      (node (ref "U1") (pin "38") (pinfunction "PE7_38") (pintype "bidirectional"))
      (node (ref "U1") (pin "49") (pinfunction "GND_49_49") (pintype "bidirectional"))
      (node (ref "U1") (pin "5") (pinfunction "PE6_5") (pintype "bidirectional"))
      (node (ref "U1") (pin "73") (pinfunction "PF6_73") (pintype "bidirectional"))
      (node (ref "U1") (pin "74") (pinfunction "GND_74_74") (pintype "bidirectional"))
      (node (ref "U1") (pin "77") (pinfunction "PA15_77") (pintype "bidirectional"))
      (node (ref "U1") (pin "94") (pinfunction "BOOT0_94") (pintype "bidirectional"))
      (node (ref "U1") (pin "99") (pinfunction "GND_99_99") (pintype "bidirectional"))
      (node (ref "U10") (pin "10") (pinfunction "GND_10") (pintype "bidirectional"))
      (node (ref "U2") (pin "12") (pinfunction "GND_12_12") (pintype "bidirectional"))
      (node (ref "U2") (pin "34") (pinfunction "GND_34_34") (pintype "bidirectional"))
      (node (ref "U3") (pin "14") (pinfunction "PB0_14") (pintype "bidirectional"))
      (node (ref "U3") (pin "15") (pinfunction "PB1_15") (pintype "bidirectional"))
      (node (ref "U3") (pin "16") (pinfunction "GND_16_16") (pintype "bidirectional"))
      (node (ref "U3") (pin "22") (pinfunction "PA12_22") (pintype "bidirectional"))
      (node (ref "U3") (pin "26") (pinfunction "PB3_26") (pintype "bidirectional"))
      (node (ref "U3") (pin "27") (pinfunction "PB4_27") (pintype "bidirectional"))
      (node (ref "U3") (pin "28") (pinfunction "PB5_28") (pintype "bidirectional"))
      (node (ref "U3") (pin "29") (pinfunction "PB6_29") (pintype "bidirectional"))
      (node (ref "U3") (pin "30") (pinfunction "PB7_30") (pintype "bidirectional"))
      (node (ref "U3") (pin "31") (pinfunction "BOOT0_31") (pintype "bidirectional"))
      (node (ref "U3") (pin "32") (pinfunction "GND_32_32") (pintype "bidirectional"))
      (node (ref "U5") (pin "14") (pinfunction "PB0_14") (pintype "bidirectional"))
      (node (ref "U5") (pin "15") (pinfunction "PB1_15") (pintype "bidirectional"))
      (node (ref "U5") (pin "16") (pinfunction "GND_16_16") (pintype "bidirectional"))
      (node (ref "U5") (pin "22") (pinfunction "PA12_22") (pintype "bidirectional"))
      (node (ref "U5") (pin "26") (pinfunction "PB3_26") (pintype "bidirectional"))
      (node (ref "U5") (pin "27") (pinfunction "PB4_27") (pintype "bidirectional"))
      (node (ref "U5") (pin "28") (pinfunction "PB5_28") (pintype "bidirectional"))
      (node (ref "U5") (pin "29") (pinfunction "PB6_29") (pintype "bidirectional"))
      (node (ref "U5") (pin "30") (pinfunction "PB7_30") (pintype "bidirectional"))
      (node (ref "U5") (pin "31") (pinfunction "BOOT0_31") (pintype "bidirectional"))
      (node (ref "U5") (pin "32") (pinfunction "GND_32_32") (pintype "bidirectional"))
      (node (ref "U6") (pin "14") (pinfunction "PB0_14") (pintype "bidirectional"))
      (node (ref "U6") (pin "15") (pinfunction "PB1_15") (pintype "bidirectional"))
      (node (ref "U6") (pin "16") (pinfunction "GND_16_16") (pintype "bidirectional"))
      (node (ref "U6") (pin "22") (pinfunction "PA12_22") (pintype "bidirectional"))
      (node (ref "U6") (pin "26") (pinfunction "PB3_26") (pintype "bidirectional"))
      (node (ref "U6") (pin "27") (pinfunction "PB4_27") (pintype "bidirectional"))
      (node (ref "U6") (pin "28") (pinfunction "PB5_28") (pintype "bidirectional"))
      (node (ref "U6") (pin "29") (pinfunction "PB6_29") (pintype "bidirectional"))
      (node (ref "U6") (pin "30") (pinfunction "PB7_30") (pintype "bidirectional"))
      (node (ref "U6") (pin "31") (pinfunction "BOOT0_31") (pintype "bidirectional"))
      (node (ref "U6") (pin "32") (pinfunction "GND_32_32") (pintype "bidirectional"))
      (node (ref "U7") (pin "14") (pinfunction "PB0_14") (pintype "bidirectional"))
      (node (ref "U7") (pin "15") (pinfunction "PB1_15") (pintype "bidirectional"))
      (node (ref "U7") (pin "16") (pinfunction "GND_16_16") (pintype "bidirectional"))
      (node (ref "U7") (pin "22") (pinfunction "PA12_22") (pintype "bidirectional"))
      (node (ref "U7") (pin "26") (pinfunction "PB3_26") (pintype "bidirectional"))
      (node (ref "U7") (pin "27") (pinfunction "PB4_27") (pintype "bidirectional"))
      (node (ref "U7") (pin "28") (pinfunction "PB5_28") (pintype "bidirectional"))
      (node (ref "U7") (pin "29") (pinfunction "PB6_29") (pintype "bidirectional"))
      (node (ref "U7") (pin "30") (pinfunction "PB7_30") (pintype "bidirectional"))
      (node (ref "U7") (pin "31") (pinfunction "BOOT0_31") (pintype "bidirectional"))
      (node (ref "U7") (pin "32") (pinfunction "GND_32_32") (pintype "bidirectional"))
      (node (ref "U8") (pin "2") (pinfunction "GND_2") (pintype "bidirectional"))
      (node (ref "U9") (pin "14") (pinfunction "PB0_14") (pintype "bidirectional"))
      (node (ref "U9") (pin "15") (pinfunction "PB1_15") (pintype "bidirectional"))
      (node (ref "U9") (pin "16") (pinfunction "GND_16_16") (pintype "bidirectional"))
      (node (ref "U9") (pin "22") (pinfunction "PA12_22") (pintype "bidirectional"))
      (node (ref "U9") (pin "26") (pinfunction "PB3_26") (pintype "bidirectional"))
      (node (ref "U9") (pin "31") (pinfunction "BOOT0_31") (pintype "bidirectional"))
      (node (ref "U9") (pin "32") (pinfunction "GND_32_32") (pintype "bidirectional"))
    )
    (net (code "2") (name "Net-(D1-Pad1)") (class "Default")
      (node (ref "D1") (pin "1") (pinfunction "1_1") (pintype "bidirectional"))
      (node (ref "R1") (pin "1") (pinfunction "1_1") (pintype "bidirectional"))
    )
    (net (code "3") (name "Net-(D2-Pad1)") (class "Default")
      (node (ref "D2") (pin "1") (pinfunction "1_1") (pintype "bidirectional"))
      (node (ref "R2") (pin "1") (pinfunction "1_1") (pintype "bidirectional"))
    )
    (net (code "4") (name "Net-(D3-Pad1)") (class "Default")
      (node (ref "D3") (pin "1") (pinfunction "1_1") (pintype "bidirectional"))
      (node (ref "R3") (pin "1") (pinfunction "1_1") (pintype "bidirectional"))
    )
    (net (code "5") (name "Net-(D4-Pad1)") (class "Default")
      (node (ref "D4") (pin "1") (pinfunction "1_1") (pintype "bidirectional"))
      (node (ref "R4") (pin "1") (pinfunction "1_1") (pintype "bidirectional"))
    )
    (net (code "6") (name "Net-(D5-Pad1)") (class "Default")
      (node (ref "D5") (pin "1") (pinfunction "1_1") (pintype "bidirectional"))
      (node (ref "R5") (pin "1") (pinfunction "1_1") (pintype "bidirectional"))
    )
    (net (code "7") (name "Net-(D6-Pad1)") (class "Default")
      (node (ref "D6") (pin "1") (pinfunction "1_1") (pintype "bidirectional"))
      (node (ref "R6") (pin "1") (pinfunction "1_1") (pintype "bidirectional"))
    )
    (net (code "8") (name "Net-(D7-Pad1)") (class "Default")
      (node (ref "D7") (pin "1") (pinfunction "1_1") (pintype "bidirectional"))
      (node (ref "R7") (pin "1") (pinfunction "1_1") (pintype "bidirectional"))
    )
    (net (code "9") (name "Net-(U1-PA0)") (class "Default")
      (node (ref "U1") (pin "23") (pinfunction "PA0_23") (pintype "bidirectional"))
      (node (ref "U2") (pin "9") (pinfunction "DQ0_9") (pintype "bidirectional"))
    )
    (net (code "10") (name "Net-(U1-PA1)") (class "Default")
      (node (ref "U1") (pin "24") (pinfunction "PA1_24") (pintype "bidirectional"))
      (node (ref "U2") (pin "10") (pinfunction "DQ1_10") (pintype "bidirectional"))
    )
    (net (code "11") (name "Net-(U1-PA2)") (class "Default")
      (node (ref "U1") (pin "25") (pinfunction "PA2_25") (pintype "bidirectional"))
      (node (ref "U2") (pin "13") (pinfunction "DQ2_13") (pintype "bidirectional"))
    )
    (net (code "12") (name "Net-(U1-PA3)") (class "Default")
      (node (ref "U1") (pin "26") (pinfunction "PA3_26") (pintype "bidirectional"))
      (node (ref "U2") (pin "14") (pinfunction "DQ3_14") (pintype "bidirectional"))
    )
    (net (code "13") (name "Net-(U1-PA4)") (class "Default")
      (node (ref "U1") (pin "29") (pinfunction "PA4_29") (pintype "bidirectional"))
      (node (ref "U2") (pin "31") (pinfunction "DQ4_31") (pintype "bidirectional"))
    )
    (net (code "14") (name "Net-(U1-PA5)") (class "Default")
      (node (ref "U1") (pin "30") (pinfunction "PA5_30") (pintype "bidirectional"))
      (node (ref "U2") (pin "32") (pinfunction "DQ5_32") (pintype "bidirectional"))
    )
    (net (code "15") (name "Net-(U1-PA6)") (class "Default")
      (node (ref "U1") (pin "31") (pinfunction "PA6_31") (pintype "bidirectional"))
      (node (ref "U2") (pin "35") (pinfunction "DQ6_35") (pintype "bidirectional"))
    )
    (net (code "16") (name "Net-(U1-PA7)") (class "Default")
      (node (ref "U1") (pin "32") (pinfunction "PA7_32") (pintype "bidirectional"))
      (node (ref "U2") (pin "36") (pinfunction "DQ7_36") (pintype "bidirectional"))
    )
    (net (code "17") (name "Net-(U1-PA8)") (class "Default")
      (node (ref "U1") (pin "67") (pinfunction "PA8_67") (pintype "bidirectional"))
      (node (ref "U2") (pin "21") (pinfunction "A16_21") (pintype "bidirectional"))
    )
    (net (code "18") (name "Net-(U1-PA9)") (class "Default")
      (node (ref "U1") (pin "68") (pinfunction "PA9_68") (pintype "bidirectional"))
      (node (ref "U2") (pin "20") (pinfunction "A17_20") (pintype "bidirectional"))
    )
    (net (code "19") (name "Net-(U1-PA10)") (class "Default")
      (node (ref "U1") (pin "69") (pinfunction "PA10_69") (pintype "bidirectional"))
      (node (ref "U2") (pin "19") (pinfunction "A18_19") (pintype "bidirectional"))
    )
    (net (code "20") (name "Net-(U1-PA11)") (class "Default")
      (node (ref "U1") (pin "70") (pinfunction "PA11_70") (pintype "bidirectional"))
      (node (ref "U2") (pin "18") (pinfunction "A19_18") (pintype "bidirectional"))
    )
    (net (code "21") (name "Net-(U1-PA12)") (class "Default")
      (node (ref "U1") (pin "71") (pinfunction "PA12_71") (pintype "bidirectional"))
      (node (ref "U2") (pin "16") (pinfunction "A20_16") (pintype "bidirectional"))
    )
    (net (code "22") (name "Net-(U1-PA13{slash}SWDIO)") (class "Default")
      (node (ref "P6") (pin "2") (pinfunction "2_2") (pintype "bidirectional"))
      (node (ref "U1") (pin "72") (pinfunction "PA13/SWDIO_72") (pintype "bidirectional"))
    )
    (net (code "23") (name "Net-(U1-PA14{slash}SWCLK)") (class "Default")
      (node (ref "P6") (pin "1") (pinfunction "1_1") (pintype "bidirectional"))
      (node (ref "U1") (pin "76") (pinfunction "PA14/SWCLK_76") (pintype "bidirectional"))
    )
    (net (code "24") (name "Net-(U1-PB0)") (class "Default")
      (node (ref "U1") (pin "35") (pinfunction "PB0_35") (pintype "bidirectional"))
      (node (ref "U3") (pin "20") (pinfunction "PA10_20") (pintype "bidirectional"))
    )
    (net (code "25") (name "Net-(U1-PB1)") (class "Default")
      (node (ref "U1") (pin "36") (pinfunction "PB1_36") (pintype "bidirectional"))
      (node (ref "U5") (pin "20") (pinfunction "PA10_20") (pintype "bidirectional"))
    )
    (net (code "26") (name "Net-(U1-PB2)") (class "Default")
      (node (ref "U1") (pin "37") (pinfunction "PB2_37") (pintype "bidirectional"))
      (node (ref "U6") (pin "20") (pinfunction "PA10_20") (pintype "bidirectional"))
    )
    (net (code "27") (name "Net-(U1-PB3)") (class "Default")
      (node (ref "U1") (pin "89") (pinfunction "PB3_89") (pintype "bidirectional"))
      (node (ref "U7") (pin "20") (pinfunction "PA10_20") (pintype "bidirectional"))
    )
    (net (code "28") (name "Net-(U1-PB4)") (class "Default")
      (node (ref "U1") (pin "90") (pinfunction "PB4_90") (pintype "bidirectional"))
      (node (ref "U9") (pin "20") (pinfunction "PA10_20") (pintype "bidirectional"))
    )
    (net (code "29") (name "Net-(U1-PB5)") (class "Default")
      (node (ref "P3") (pin "1") (pinfunction "1_1") (pintype "bidirectional"))
      (node (ref "U1") (pin "91") (pinfunction "PB5_91") (pintype "bidirectional"))
    )
    (net (code "30") (name "Net-(U1-PB6)") (class "Default")
      (node (ref "P3") (pin "2") (pinfunction "2_2") (pintype "bidirectional"))
      (node (ref "U1") (pin "92") (pinfunction "PB6_92") (pintype "bidirectional"))
    )
    (net (code "31") (name "Net-(U1-PB7)") (class "Default")
      (node (ref "P3") (pin "3") (pinfunction "3_3") (pintype "bidirectional"))
      (node (ref "U1") (pin "93") (pinfunction "PB7_93") (pintype "bidirectional"))
    )
    (net (code "32") (name "Net-(U1-PB8)") (class "Default")
      (node (ref "P3") (pin "4") (pinfunction "4_4") (pintype "bidirectional"))
      (node (ref "U1") (pin "95") (pinfunction "PB8_95") (pintype "bidirectional"))
    )
    (net (code "33") (name "Net-(U1-PB9)") (class "Default")
      (node (ref "P3") (pin "5") (pinfunction "5_5") (pintype "bidirectional"))
      (node (ref "U1") (pin "96") (pinfunction "PB9_96") (pintype "bidirectional"))
    )
    (net (code "34") (name "Net-(U1-PB10)") (class "Default")
      (node (ref "P3") (pin "6") (pinfunction "6_6") (pintype "bidirectional"))
      (node (ref "U1") (pin "47") (pinfunction "PB10_47") (pintype "bidirectional"))
    )
    (net (code "35") (name "Net-(U1-PB11)") (class "Default")
      (node (ref "P3") (pin "7") (pinfunction "7_7") (pintype "bidirectional"))
      (node (ref "U1") (pin "48") (pinfunction "PB11_48") (pintype "bidirectional"))
    )
    (net (code "36") (name "Net-(U1-PB12)") (class "Default")
      (node (ref "P3") (pin "8") (pinfunction "8_8") (pintype "bidirectional"))
      (node (ref "U1") (pin "51") (pinfunction "PB12_51") (pintype "bidirectional"))
    )
    (net (code "37") (name "Net-(U1-PB13)") (class "Default")
      (node (ref "P3") (pin "9") (pinfunction "9_9") (pintype "bidirectional"))
      (node (ref "U1") (pin "52") (pinfunction "PB13_52") (pintype "bidirectional"))
    )
    (net (code "38") (name "Net-(U1-PB14)") (class "Default")
      (node (ref "P3") (pin "10") (pinfunction "10_10") (pintype "bidirectional"))
      (node (ref "U1") (pin "53") (pinfunction "PB14_53") (pintype "bidirectional"))
    )
    (net (code "39") (name "Net-(U1-PB15)") (class "Default")
      (node (ref "P3") (pin "11") (pinfunction "11_11") (pintype "bidirectional"))
      (node (ref "U1") (pin "54") (pinfunction "PB15_54") (pintype "bidirectional"))
    )
    (net (code "40") (name "Net-(U1-PC0)") (class "Default")
      (node (ref "U1") (pin "15") (pinfunction "PC0_15") (pintype "bidirectional"))
      (node (ref "U3") (pin "21") (pinfunction "PA11_21") (pintype "bidirectional"))
    )
    (net (code "41") (name "Net-(U1-PC1)") (class "Default")
      (node (ref "U1") (pin "16") (pinfunction "PC1_16") (pintype "bidirectional"))
      (node (ref "U5") (pin "21") (pinfunction "PA11_21") (pintype "bidirectional"))
    )
    (net (code "42") (name "Net-(U1-PC2)") (class "Default")
      (node (ref "U1") (pin "17") (pinfunction "PC2_17") (pintype "bidirectional"))
      (node (ref "U6") (pin "21") (pinfunction "PA11_21") (pintype "bidirectional"))
    )
    (net (code "43") (name "Net-(U1-PC3)") (class "Default")
      (node (ref "U1") (pin "18") (pinfunction "PC3_18") (pintype "bidirectional"))
      (node (ref "U7") (pin "21") (pinfunction "PA11_21") (pintype "bidirectional"))
    )
    (net (code "44") (name "Net-(U1-PC4)") (class "Default")
      (node (ref "U1") (pin "33") (pinfunction "PC4_33") (pintype "bidirectional"))
      (node (ref "U9") (pin "21") (pinfunction "PA11_21") (pintype "bidirectional"))
    )
    (net (code "45") (name "Net-(U1-PC5)") (class "Default")
      (node (ref "P4") (pin "1") (pinfunction "1_1") (pintype "bidirectional"))
      (node (ref "U1") (pin "34") (pinfunction "PC5_34") (pintype "bidirectional"))
    )
    (net (code "46") (name "Net-(U1-PC6)") (class "Default")
      (node (ref "P4") (pin "2") (pinfunction "2_2") (pintype "bidirectional"))
      (node (ref "U1") (pin "63") (pinfunction "PC6_63") (pintype "bidirectional"))
    )
    (net (code "47") (name "Net-(U1-PC7)") (class "Default")
      (node (ref "P4") (pin "3") (pinfunction "3_3") (pintype "bidirectional"))
      (node (ref "U1") (pin "64") (pinfunction "PC7_64") (pintype "bidirectional"))
    )
    (net (code "48") (name "Net-(U1-PC8)") (class "Default")
      (node (ref "P4") (pin "4") (pinfunction "4_4") (pintype "bidirectional"))
      (node (ref "U1") (pin "65") (pinfunction "PC8_65") (pintype "bidirectional"))
    )
    (net (code "49") (name "Net-(U1-PC9)") (class "Default")
      (node (ref "P4") (pin "5") (pinfunction "5_5") (pintype "bidirectional"))
      (node (ref "U1") (pin "66") (pinfunction "PC9_66") (pintype "bidirectional"))
    )
    (net (code "50") (name "Net-(U1-PC10)") (class "Default")
      (node (ref "P4") (pin "6") (pinfunction "6_6") (pintype "bidirectional"))
      (node (ref "U1") (pin "78") (pinfunction "PC10_78") (pintype "bidirectional"))
    )
    (net (code "51") (name "Net-(U1-PC11)") (class "Default")
      (node (ref "P4") (pin "7") (pinfunction "7_7") (pintype "bidirectional"))
      (node (ref "U1") (pin "79") (pinfunction "PC11_79") (pintype "bidirectional"))
    )
    (net (code "52") (name "Net-(U1-PC12)") (class "Default")
      (node (ref "P4") (pin "8") (pinfunction "8_8") (pintype "bidirectional"))
      (node (ref "U1") (pin "80") (pinfunction "PC12_80") (pintype "bidirectional"))
    )
    (net (code "53") (name "Net-(U1-PC13)") (class "Default")
      (node (ref "P4") (pin "9") (pinfunction "9_9") (pintype "bidirectional"))
      (node (ref "U1") (pin "7") (pinfunction "PC13_7") (pintype "bidirectional"))
    )
    (net (code "54") (name "Net-(U1-PC14{slash}OSC32_IN)") (class "Default")
      (node (ref "P4") (pin "10") (pinfunction "10_10") (pintype "bidirectional"))
      (node (ref "U1") (pin "8") (pinfunction "PC14/OSC32_IN_8") (pintype "bidirectional"))
    )
    (net (code "55") (name "Net-(U1-PC15{slash}OSC32_OUT)") (class "Default")
      (node (ref "P4") (pin "11") (pinfunction "11_11") (pintype "bidirectional"))
      (node (ref "U1") (pin "9") (pinfunction "PC15/OSC32_OUT_9") (pintype "bidirectional"))
    )
    (net (code "56") (name "Net-(U1-PD0)") (class "Default")
      (node (ref "U1") (pin "81") (pinfunction "PD0_81") (pintype "bidirectional"))
      (node (ref "U2") (pin "5") (pinfunction "A0_5") (pintype "bidirectional"))
    )
    (net (code "57") (name "Net-(U1-PD1)") (class "Default")
      (node (ref "U1") (pin "82") (pinfunction "PD1_82") (pintype "bidirectional"))
      (node (ref "U2") (pin "4") (pinfunction "A1_4") (pintype "bidirectional"))
    )
    (net (code "58") (name "Net-(U1-PD2)") (class "Default")
      (node (ref "U1") (pin "83") (pinfunction "PD2_83") (pintype "bidirectional"))
      (node (ref "U2") (pin "3") (pinfunction "A2_3") (pintype "bidirectional"))
    )
    (net (code "59") (name "Net-(U1-PD3)") (class "Default")
      (node (ref "U1") (pin "84") (pinfunction "PD3_84") (pintype "bidirectional"))
      (node (ref "U2") (pin "2") (pinfunction "A3_2") (pintype "bidirectional"))
    )
    (net (code "60") (name "Net-(U1-PD4)") (class "Default")
      (node (ref "U1") (pin "85") (pinfunction "PD4_85") (pintype "bidirectional"))
      (node (ref "U2") (pin "1") (pinfunction "A4_1") (pintype "bidirectional"))
    )
    (net (code "61") (name "Net-(U1-PD5)") (class "Default")
      (node (ref "U1") (pin "86") (pinfunction "PD5_86") (pintype "bidirectional"))
      (node (ref "U2") (pin "44") (pinfunction "A5_44") (pintype "bidirectional"))
    )
    (net (code "62") (name "Net-(U1-PD6)") (class "Default")
      (node (ref "U1") (pin "87") (pinfunction "PD6_87") (pintype "bidirectional"))
      (node (ref "U2") (pin "43") (pinfunction "A6_43") (pintype "bidirectional"))
    )
    (net (code "63") (name "Net-(U1-PD7)") (class "Default")
      (node (ref "U1") (pin "88") (pinfunction "PD7_88") (pintype "bidirectional"))
      (node (ref "U2") (pin "42") (pinfunction "A7_42") (pintype "bidirectional"))
    )
    (net (code "64") (name "Net-(U1-PD8)") (class "Default")
      (node (ref "U1") (pin "55") (pinfunction "PD8_55") (pintype "bidirectional"))
      (node (ref "U2") (pin "39") (pinfunction "A8_39") (pintype "bidirectional"))
    )
    (net (code "65") (name "Net-(U1-PD9)") (class "Default")
      (node (ref "U1") (pin "56") (pinfunction "PD9_56") (pintype "bidirectional"))
      (node (ref "U2") (pin "28") (pinfunction "A9_28") (pintype "bidirectional"))
    )
    (net (code "66") (name "Net-(U1-PD10)") (class "Default")
      (node (ref "U1") (pin "57") (pinfunction "PD10_57") (pintype "bidirectional"))
      (node (ref "U2") (pin "27") (pinfunction "A10_27") (pintype "bidirectional"))
    )
    (net (code "67") (name "Net-(U1-PD11)") (class "Default")
      (node (ref "U1") (pin "58") (pinfunction "PD11_58") (pintype "bidirectional"))
      (node (ref "U2") (pin "26") (pinfunction "A11_26") (pintype "bidirectional"))
    )
    (net (code "68") (name "Net-(U1-PD12)") (class "Default")
      (node (ref "U1") (pin "59") (pinfunction "PD12_59") (pintype "bidirectional"))
      (node (ref "U2") (pin "25") (pinfunction "A12_25") (pintype "bidirectional"))
    )
    (net (code "69") (name "Net-(U1-PD13)") (class "Default")
      (node (ref "U1") (pin "60") (pinfunction "PD13_60") (pintype "bidirectional"))
      (node (ref "U2") (pin "24") (pinfunction "A13_24") (pintype "bidirectional"))
    )
    (net (code "70") (name "Net-(U1-PD14)") (class "Default")
      (node (ref "U1") (pin "61") (pinfunction "PD14_61") (pintype "bidirectional"))
      (node (ref "U2") (pin "23") (pinfunction "A14_23") (pintype "bidirectional"))
    )
    (net (code "71") (name "Net-(U1-PD15)") (class "Default")
      (node (ref "U1") (pin "62") (pinfunction "PD15_62") (pintype "bidirectional"))
      (node (ref "U2") (pin "22") (pinfunction "A15_22") (pintype "bidirectional"))
    )
    (net (code "72") (name "Net-(U1-PE0)") (class "Default")
      (node (ref "P2") (pin "1") (pinfunction "1_1") (pintype "bidirectional"))
      (node (ref "U1") (pin "97") (pinfunction "PE0_97") (pintype "bidirectional"))
      (node (ref "U3") (pin "18") (pinfunction "PA8_18") (pintype "bidirectional"))
      (node (ref "U5") (pin "18") (pinfunction "PA8_18") (pintype "bidirectional"))
      (node (ref "U6") (pin "18") (pinfunction "PA8_18") (pintype "bidirectional"))
      (node (ref "U7") (pin "18") (pinfunction "PA8_18") (pintype "bidirectional"))
      (node (ref "U9") (pin "18") (pinfunction "PA8_18") (pintype "bidirectional"))
    )
    (net (code "73") (name "Net-(U1-PE1)") (class "Default")
      (node (ref "P2") (pin "2") (pinfunction "2_2") (pintype "bidirectional"))
      (node (ref "U1") (pin "98") (pinfunction "PE1_98") (pintype "bidirectional"))
      (node (ref "U3") (pin "19") (pinfunction "PA9_19") (pintype "bidirectional"))
      (node (ref "U5") (pin "19") (pinfunction "PA9_19") (pintype "bidirectional"))
      (node (ref "U6") (pin "19") (pinfunction "PA9_19") (pintype "bidirectional"))
      (node (ref "U7") (pin "19") (pinfunction "PA9_19") (pintype "bidirectional"))
      (node (ref "U9") (pin "19") (pinfunction "PA9_19") (pintype "bidirectional"))
    )
    (net (code "74") (name "Net-(U1-PE2)") (class "Default")
      (node (ref "U1") (pin "1") (pinfunction "PE2_1") (pintype "bidirectional"))
      (node (ref "U2") (pin "41") (pinfunction "~{OE}_41") (pintype "bidirectional"))
    )
    (net (code "75") (name "Net-(U1-PE3)") (class "Default")
      (node (ref "U1") (pin "2") (pinfunction "PE3_2") (pintype "bidirectional"))
      (node (ref "U2") (pin "17") (pinfunction "~{WE}_17") (pintype "bidirectional"))
    )
    (net (code "76") (name "Net-(U1-PE4)") (class "Default")
      (node (ref "U1") (pin "3") (pinfunction "PE4_3") (pintype "bidirectional"))
      (node (ref "U2") (pin "40") (pinfunction "CE2_40") (pintype "bidirectional"))
    )
    (net (code "77") (name "Net-(U1-PE5)") (class "Default")
      (node (ref "U1") (pin "4") (pinfunction "PE5_4") (pintype "bidirectional"))
      (node (ref "U2") (pin "6") (pinfunction "~{CE}_6") (pintype "bidirectional"))
    )
    (net (code "78") (name "Net-(U1-PE8)") (class "Default")
      (node (ref "P1") (pin "1") (pinfunction "1_1") (pintype "bidirectional"))
      (node (ref "U1") (pin "39") (pinfunction "PE8_39") (pintype "bidirectional"))
      (node (ref "U3") (pin "6") (pinfunction "PA0_6") (pintype "bidirectional"))
      (node (ref "U5") (pin "6") (pinfunction "PA0_6") (pintype "bidirectional"))
      (node (ref "U6") (pin "6") (pinfunction "PA0_6") (pintype "bidirectional"))
      (node (ref "U7") (pin "6") (pinfunction "PA0_6") (pintype "bidirectional"))
      (node (ref "U9") (pin "6") (pinfunction "PA0_6") (pintype "bidirectional"))
    )
    (net (code "79") (name "Net-(U1-PE9)") (class "Default")
      (node (ref "P1") (pin "2") (pinfunction "2_2") (pintype "bidirectional"))
      (node (ref "U1") (pin "40") (pinfunction "PE9_40") (pintype "bidirectional"))
      (node (ref "U3") (pin "7") (pinfunction "PA1_7") (pintype "bidirectional"))
      (node (ref "U5") (pin "7") (pinfunction "PA1_7") (pintype "bidirectional"))
      (node (ref "U6") (pin "7") (pinfunction "PA1_7") (pintype "bidirectional"))
      (node (ref "U7") (pin "7") (pinfunction "PA1_7") (pintype "bidirectional"))
      (node (ref "U9") (pin "7") (pinfunction "PA1_7") (pintype "bidirectional"))
    )
    (net (code "80") (name "Net-(U1-PE10)") (class "Default")
      (node (ref "P1") (pin "3") (pinfunction "3_3") (pintype "bidirectional"))
      (node (ref "U1") (pin "41") (pinfunction "PE10_41") (pintype "bidirectional"))
      (node (ref "U3") (pin "8") (pinfunction "PA2_8") (pintype "bidirectional"))
      (node (ref "U5") (pin "8") (pinfunction "PA2_8") (pintype "bidirectional"))
      (node (ref "U6") (pin "8") (pinfunction "PA2_8") (pintype "bidirectional"))
      (node (ref "U7") (pin "8") (pinfunction "PA2_8") (pintype "bidirectional"))
      (node (ref "U9") (pin "8") (pinfunction "PA2_8") (pintype "bidirectional"))
    )
    (net (code "81") (name "Net-(U1-PE11)") (class "Default")
      (node (ref "P1") (pin "4") (pinfunction "4_4") (pintype "bidirectional"))
      (node (ref "U1") (pin "42") (pinfunction "PE11_42") (pintype "bidirectional"))
      (node (ref "U3") (pin "9") (pinfunction "PA3_9") (pintype "bidirectional"))
      (node (ref "U5") (pin "9") (pinfunction "PA3_9") (pintype "bidirectional"))
      (node (ref "U6") (pin "9") (pinfunction "PA3_9") (pintype "bidirectional"))
      (node (ref "U7") (pin "9") (pinfunction "PA3_9") (pintype "bidirectional"))
      (node (ref "U9") (pin "9") (pinfunction "PA3_9") (pintype "bidirectional"))
    )
    (net (code "82") (name "Net-(U1-PE12)") (class "Default")
      (node (ref "P1") (pin "5") (pinfunction "5_5") (pintype "bidirectional"))
      (node (ref "U1") (pin "43") (pinfunction "PE12_43") (pintype "bidirectional"))
      (node (ref "U3") (pin "10") (pinfunction "PA4_10") (pintype "bidirectional"))
      (node (ref "U5") (pin "10") (pinfunction "PA4_10") (pintype "bidirectional"))
      (node (ref "U6") (pin "10") (pinfunction "PA4_10") (pintype "bidirectional"))
      (node (ref "U7") (pin "10") (pinfunction "PA4_10") (pintype "bidirectional"))
      (node (ref "U9") (pin "10") (pinfunction "PA4_10") (pintype "bidirectional"))
    )
    (net (code "83") (name "Net-(U1-PE13)") (class "Default")
      (node (ref "P1") (pin "6") (pinfunction "6_6") (pintype "bidirectional"))
      (node (ref "U1") (pin "44") (pinfunction "PE13_44") (pintype "bidirectional"))
      (node (ref "U3") (pin "11") (pinfunction "PA5_11") (pintype "bidirectional"))
      (node (ref "U5") (pin "11") (pinfunction "PA5_11") (pintype "bidirectional"))
      (node (ref "U6") (pin "11") (pinfunction "PA5_11") (pintype "bidirectional"))
      (node (ref "U7") (pin "11") (pinfunction "PA5_11") (pintype "bidirectional"))
      (node (ref "U9") (pin "11") (pinfunction "PA5_11") (pintype "bidirectional"))
    )
    (net (code "84") (name "Net-(U1-PE14)") (class "Default")
      (node (ref "P1") (pin "7") (pinfunction "7_7") (pintype "bidirectional"))
      (node (ref "U1") (pin "45") (pinfunction "PE14_45") (pintype "bidirectional"))
      (node (ref "U3") (pin "12") (pinfunction "PA6_12") (pintype "bidirectional"))
      (node (ref "U5") (pin "12") (pinfunction "PA6_12") (pintype "bidirectional"))
      (node (ref "U6") (pin "12") (pinfunction "PA6_12") (pintype "bidirectional"))
      (node (ref "U7") (pin "12") (pinfunction "PA6_12") (pintype "bidirectional"))
      (node (ref "U9") (pin "12") (pinfunction "PA6_12") (pintype "bidirectional"))
    )
    (net (code "85") (name "Net-(U1-PE15)") (class "Default")
      (node (ref "P1") (pin "8") (pinfunction "8_8") (pintype "bidirectional"))
      (node (ref "U1") (pin "46") (pinfunction "PE15_46") (pintype "bidirectional"))
      (node (ref "U3") (pin "13") (pinfunction "PA7_13") (pintype "bidirectional"))
      (node (ref "U5") (pin "13") (pinfunction "PA7_13") (pintype "bidirectional"))
      (node (ref "U6") (pin "13") (pinfunction "PA7_13") (pintype "bidirectional"))
      (node (ref "U7") (pin "13") (pinfunction "PA7_13") (pintype "bidirectional"))
      (node (ref "U9") (pin "13") (pinfunction "PA7_13") (pintype "bidirectional"))
    )
    (net (code "86") (name "Net-(U1-PF0{slash}OSC_IN)") (class "Default")
      (node (ref "C1") (pin "2") (pinfunction "2_2") (pintype "bidirectional"))
      (node (ref "U1") (pin "12") (pinfunction "PF0/OSC_IN_12") (pintype "bidirectional"))
      (node (ref "X1") (pin "1") (pinfunction "1_1") (pintype "bidirectional"))
    )
    (net (code "87") (name "Net-(U1-PF1{slash}OSC_OUT)") (class "Default")
      (node (ref "C2") (pin "2") (pinfunction "2_2") (pintype "bidirectional"))
      (node (ref "U1") (pin "13") (pinfunction "PF1/OSC_OUT_13") (pintype "bidirectional"))
      (node (ref "X1") (pin "2") (pinfunction "2_2") (pintype "bidirectional"))
    )
    (net (code "88") (name "Net-(U1-PF9)") (class "Default")
      (node (ref "R6") (pin "2") (pinfunction "2_2") (pintype "bidirectional"))
      (node (ref "U1") (pin "10") (pinfunction "PF9_10") (pintype "bidirectional"))
    )
    (net (code "89") (name "Net-(U1-~{RST})") (class "Default")
      (node (ref "P12") (pin "2") (pinfunction "2_2") (pintype "bidirectional"))
      (node (ref "P5") (pin "3") (pinfunction "3_3") (pintype "bidirectional"))
      (node (ref "U1") (pin "14") (pinfunction "~{RST}_14") (pintype "bidirectional"))
      (node (ref "U3") (pin "4") (pinfunction "~{RST}_4") (pintype "bidirectional"))
      (node (ref "U5") (pin "4") (pinfunction "~{RST}_4") (pintype "bidirectional"))
      (node (ref "U6") (pin "4") (pinfunction "~{RST}_4") (pintype "bidirectional"))
      (node (ref "U7") (pin "4") (pinfunction "~{RST}_4") (pintype "bidirectional"))
      (node (ref "U9") (pin "4") (pinfunction "~{RST}_4") (pintype "bidirectional"))
    )
    (net (code "90") (name "Net-(U3-PA13{slash}SWDIO)") (class "Default")
      (node (ref "P7") (pin "2") (pinfunction "2_2") (pintype "bidirectional"))
      (node (ref "U3") (pin "23") (pinfunction "PA13/SWDIO_23") (pintype "bidirectional"))
    )
    (net (code "91") (name "Net-(U3-PA14{slash}SWCLK)") (class "Default")
      (node (ref "P7") (pin "1") (pinfunction "1_1") (pintype "bidirectional"))
      (node (ref "U3") (pin "24") (pinfunction "PA14/SWCLK_24") (pintype "bidirectional"))
    )
    (net (code "92") (name "Net-(U3-PA15)") (class "Default")
      (node (ref "R1") (pin "2") (pinfunction "2_2") (pintype "bidirectional"))
      (node (ref "U3") (pin "25") (pinfunction "PA15_25") (pintype "bidirectional"))
    )
    (net (code "93") (name "Net-(U3-PF0{slash}OSC_IN)") (class "Default")
      (node (ref "C17") (pin "2") (pinfunction "2_2") (pintype "bidirectional"))
      (node (ref "U3") (pin "2") (pinfunction "PF0/OSC_IN_2") (pintype "bidirectional"))
      (node (ref "X2") (pin "1") (pinfunction "1_1") (pintype "bidirectional"))
    )
    (net (code "94") (name "Net-(U3-PF1{slash}OSC_OUT)") (class "Default")
      (node (ref "C18") (pin "2") (pinfunction "2_2") (pintype "bidirectional"))
      (node (ref "U3") (pin "3") (pinfunction "PF1/OSC_OUT_3") (pintype "bidirectional"))
      (node (ref "X2") (pin "2") (pinfunction "2_2") (pintype "bidirectional"))
    )
    (net (code "95") (name "Net-(U5-PA13{slash}SWDIO)") (class "Default")
      (node (ref "P8") (pin "2") (pinfunction "2_2") (pintype "bidirectional"))
      (node (ref "U5") (pin "23") (pinfunction "PA13/SWDIO_23") (pintype "bidirectional"))
    )
    (net (code "96") (name "Net-(U5-PA14{slash}SWCLK)") (class "Default")
      (node (ref "P8") (pin "1") (pinfunction "1_1") (pintype "bidirectional"))
      (node (ref "U5") (pin "24") (pinfunction "PA14/SWCLK_24") (pintype "bidirectional"))
    )
    (net (code "97") (name "Net-(U5-PA15)") (class "Default")
      (node (ref "R2") (pin "2") (pinfunction "2_2") (pintype "bidirectional"))
      (node (ref "U5") (pin "25") (pinfunction "PA15_25") (pintype "bidirectional"))
    )
    (net (code "98") (name "Net-(U5-PF0{slash}OSC_IN)") (class "Default")
      (node (ref "C31") (pin "2") (pinfunction "2_2") (pintype "bidirectional"))
      (node (ref "U5") (pin "2") (pinfunction "PF0/OSC_IN_2") (pintype "bidirectional"))
      (node (ref "X4") (pin "1") (pinfunction "1_1") (pintype "bidirectional"))
    )
    (net (code "99") (name "Net-(U5-PF1{slash}OSC_OUT)") (class "Default")
      (node (ref "C32") (pin "2") (pinfunction "2_2") (pintype "bidirectional"))
      (node (ref "U5") (pin "3") (pinfunction "PF1/OSC_OUT_3") (pintype "bidirectional"))
      (node (ref "X4") (pin "2") (pinfunction "2_2") (pintype "bidirectional"))
    )
    (net (code "100") (name "Net-(U6-PA13{slash}SWDIO)") (class "Default")
      (node (ref "P9") (pin "2") (pinfunction "2_2") (pintype "bidirectional"))
      (node (ref "U6") (pin "23") (pinfunction "PA13/SWDIO_23") (pintype "bidirectional"))
    )
    (net (code "101") (name "Net-(U6-PA14{slash}SWCLK)") (class "Default")
      (node (ref "P9") (pin "1") (pinfunction "1_1") (pintype "bidirectional"))
      (node (ref "U6") (pin "24") (pinfunction "PA14/SWCLK_24") (pintype "bidirectional"))
    )
    (net (code "102") (name "Net-(U6-PA15)") (class "Default")
      (node (ref "R3") (pin "2") (pinfunction "2_2") (pintype "bidirectional"))
      (node (ref "U6") (pin "25") (pinfunction "PA15_25") (pintype "bidirectional"))
    )
    (net (code "103") (name "Net-(U6-PF0{slash}OSC_IN)") (class "Default")
      (node (ref "C38") (pin "2") (pinfunction "2_2") (pintype "bidirectional"))
      (node (ref "U6") (pin "2") (pinfunction "PF0/OSC_IN_2") (pintype "bidirectional"))
      (node (ref "X5") (pin "1") (pinfunction "1_1") (pintype "bidirectional"))
    )
    (net (code "104") (name "Net-(U6-PF1{slash}OSC_OUT)") (class "Default")
      (node (ref "C39") (pin "2") (pinfunction "2_2") (pintype "bidirectional"))
      (node (ref "U6") (pin "3") (pinfunction "PF1/OSC_OUT_3") (pintype "bidirectional"))
      (node (ref "X5") (pin "2") (pinfunction "2_2") (pintype "bidirectional"))
    )
    (net (code "105") (name "Net-(U7-PA13{slash}SWDIO)") (class "Default")
      (node (ref "P10") (pin "2") (pinfunction "2_2") (pintype "bidirectional"))
      (node (ref "U7") (pin "23") (pinfunction "PA13/SWDIO_23") (pintype "bidirectional"))
    )
    (net (code "106") (name "Net-(U7-PA14{slash}SWCLK)") (class "Default")
      (node (ref "P10") (pin "1") (pinfunction "1_1") (pintype "bidirectional"))
      (node (ref "U7") (pin "24") (pinfunction "PA14/SWCLK_24") (pintype "bidirectional"))
    )
    (net (code "107") (name "Net-(U7-PA15)") (class "Default")
      (node (ref "R4") (pin "2") (pinfunction "2_2") (pintype "bidirectional"))
      (node (ref "U7") (pin "25") (pinfunction "PA15_25") (pintype "bidirectional"))
    )
    (net (code "108") (name "Net-(U7-PF0{slash}OSC_IN)") (class "Default")
      (node (ref "C45") (pin "2") (pinfunction "2_2") (pintype "bidirectional"))
      (node (ref "U7") (pin "2") (pinfunction "PF0/OSC_IN_2") (pintype "bidirectional"))
      (node (ref "X6") (pin "1") (pinfunction "1_1") (pintype "bidirectional"))
    )
    (net (code "109") (name "Net-(U7-PF1{slash}OSC_OUT)") (class "Default")
      (node (ref "C46") (pin "2") (pinfunction "2_2") (pintype "bidirectional"))
      (node (ref "U7") (pin "3") (pinfunction "PF1/OSC_OUT_3") (pintype "bidirectional"))
      (node (ref "X6") (pin "2") (pinfunction "2_2") (pintype "bidirectional"))
    )
    (net (code "110") (name "Net-(U8-EN)") (class "Default")
      (node (ref "C47") (pin "2") (pinfunction "2_2") (pintype "bidirectional"))
      (node (ref "P5") (pin "1") (pinfunction "1_1") (pintype "bidirectional"))
      (node (ref "U8") (pin "1") (pinfunction "VIN_1") (pintype "bidirectional"))
      (node (ref "U8") (pin "3") (pinfunction "EN_3") (pintype "bidirectional"))
    )
    (net (code "111") (name "Net-(U9-PA13{slash}SWDIO)") (class "Default")
      (node (ref "P11") (pin "2") (pinfunction "2_2") (pintype "bidirectional"))
      (node (ref "U9") (pin "23") (pinfunction "PA13/SWDIO_23") (pintype "bidirectional"))
    )
    (net (code "112") (name "Net-(U9-PA14{slash}SWCLK)") (class "Default")
      (node (ref "P11") (pin "1") (pinfunction "1_1") (pintype "bidirectional"))
      (node (ref "U9") (pin "24") (pinfunction "PA14/SWCLK_24") (pintype "bidirectional"))
    )
    (net (code "113") (name "Net-(U9-PA15)") (class "Default")
      (node (ref "R5") (pin "2") (pinfunction "2_2") (pintype "bidirectional"))
      (node (ref "U9") (pin "25") (pinfunction "PA15_25") (pintype "bidirectional"))
    )
    (net (code "114") (name "Net-(U9-PF0{slash}OSC_IN)") (class "Default")
      (node (ref "C54") (pin "2") (pinfunction "2_2") (pintype "bidirectional"))
      (node (ref "U9") (pin "2") (pinfunction "PF0/OSC_IN_2") (pintype "bidirectional"))
      (node (ref "X7") (pin "1") (pinfunction "1_1") (pintype "bidirectional"))
    )
    (net (code "115") (name "Net-(U9-PF1{slash}OSC_OUT)") (class "Default")
      (node (ref "C55") (pin "2") (pinfunction "2_2") (pintype "bidirectional"))
      (node (ref "U9") (pin "3") (pinfunction "PF1/OSC_OUT_3") (pintype "bidirectional"))
      (node (ref "X7") (pin "2") (pinfunction "2_2") (pintype "bidirectional"))
    )
    (net (code "116") (name "Net-(U10-IO0{slash}SI)") (class "Default")
      (node (ref "U10") (pin "15") (pinfunction "IO0/SI_15") (pintype "bidirectional"))
      (node (ref "U9") (pin "30") (pinfunction "PB7_30") (pintype "bidirectional"))
    )
    (net (code "117") (name "Net-(U10-IO1{slash}SO)") (class "Default")
      (node (ref "U10") (pin "8") (pinfunction "IO1/SO_8") (pintype "bidirectional"))
      (node (ref "U9") (pin "27") (pinfunction "PB4_27") (pintype "bidirectional"))
    )
    (net (code "118") (name "Net-(U10-SCK)") (class "Default")
      (node (ref "U10") (pin "16") (pinfunction "SCK_16") (pintype "bidirectional"))
      (node (ref "U9") (pin "29") (pinfunction "PB6_29") (pintype "bidirectional"))
    )
    (net (code "119") (name "Net-(U10-~{CS})") (class "Default")
      (node (ref "U10") (pin "7") (pinfunction "~{CS}_7") (pintype "bidirectional"))
      (node (ref "U9") (pin "28") (pinfunction "PB5_28") (pintype "bidirectional"))
    )
    (net (code "120") (name "VCC") (class "Default")
      (node (ref "C10") (pin "2") (pinfunction "2_2") (pintype "bidirectional"))
      (node (ref "C11") (pin "2") (pinfunction "2_2") (pintype "bidirectional"))
      (node (ref "C12") (pin "1") (pinfunction "1_1") (pintype "bidirectional"))
      (node (ref "C13") (pin "1") (pinfunction "1_1") (pintype "bidirectional"))
      (node (ref "C14") (pin "1") (pinfunction "1_1") (pintype "bidirectional"))
      (node (ref "C15") (pin "1") (pinfunction "1_1") (pintype "bidirectional"))
      (node (ref "C16") (pin "2") (pinfunction "2_2") (pintype "bidirectional"))
      (node (ref "C26") (pin "1") (pinfunction "1_1") (pintype "bidirectional"))
      (node (ref "C27") (pin "1") (pinfunction "1_1") (pintype "bidirectional"))
      (node (ref "C28") (pin "1") (pinfunction "1_1") (pintype "bidirectional"))
      (node (ref "C29") (pin "1") (pinfunction "1_1") (pintype "bidirectional"))
      (node (ref "C3") (pin "2") (pinfunction "2_2") (pintype "bidirectional"))
      (node (ref "C30") (pin "2") (pinfunction "2_2") (pintype "bidirectional"))
      (node (ref "C33") (pin "1") (pinfunction "1_1") (pintype "bidirectional"))
      (node (ref "C34") (pin "1") (pinfunction "1_1") (pintype "bidirectional"))
      (node (ref "C35") (pin "1") (pinfunction "1_1") (pintype "bidirectional"))
      (node (ref "C36") (pin "1") (pinfunction "1_1") (pintype "bidirectional"))
      (node (ref "C37") (pin "2") (pinfunction "2_2") (pintype "bidirectional"))
      (node (ref "C4") (pin "2") (pinfunction "2_2") (pintype "bidirectional"))
      (node (ref "C40") (pin "1") (pinfunction "1_1") (pintype "bidirectional"))
      (node (ref "C41") (pin "1") (pinfunction "1_1") (pintype "bidirectional"))
      (node (ref "C42") (pin "1") (pinfunction "1_1") (pintype "bidirectional"))
      (node (ref "C43") (pin "1") (pinfunction "1_1") (pintype "bidirectional"))
      (node (ref "C44") (pin "2") (pinfunction "2_2") (pintype "bidirectional"))
      (node (ref "C48") (pin "2") (pinfunction "2_2") (pintype "bidirectional"))
      (node (ref "C49") (pin "1") (pinfunction "1_1") (pintype "bidirectional"))
      (node (ref "C5") (pin "1") (pinfunction "1_1") (pintype "bidirectional"))
      (node (ref "C50") (pin "1") (pinfunction "1_1") (pintype "bidirectional"))
      (node (ref "C51") (pin "1") (pinfunction "1_1") (pintype "bidirectional"))
      (node (ref "C52") (pin "1") (pinfunction "1_1") (pintype "bidirectional"))
      (node (ref "C53") (pin "2") (pinfunction "2_2") (pintype "bidirectional"))
      (node (ref "C56") (pin "2") (pinfunction "2_2") (pintype "bidirectional"))
      (node (ref "C6") (pin "2") (pinfunction "2_2") (pintype "bidirectional"))
      (node (ref "C7") (pin "1") (pinfunction "1_1") (pintype "bidirectional"))
      (node (ref "C8") (pin "2") (pinfunction "2_2") (pintype "bidirectional"))
      (node (ref "C9") (pin "2") (pinfunction "2_2") (pintype "bidirectional"))
      (node (ref "R7") (pin "2") (pinfunction "2_2") (pintype "bidirectional"))
      (node (ref "U1") (pin "100") (pinfunction "VCC_100_100") (pintype "bidirectional"))
      (node (ref "U1") (pin "21") (pinfunction "VCCA_21_21") (pintype "bidirectional"))
      (node (ref "U1") (pin "28") (pinfunction "VCC_28_28") (pintype "bidirectional"))
      (node (ref "U1") (pin "50") (pinfunction "VCC_50_50") (pintype "bidirectional"))
      (node (ref "U1") (pin "75") (pinfunction "VCCIO2_75") (pintype "bidirectional"))
      (node (ref "U10") (pin "14") (pinfunction "VIO/RFU_14") (pintype "bidirectional"))
      (node (ref "U10") (pin "2") (pinfunction "VCC_2") (pintype "bidirectional"))
      (node (ref "U10") (pin "3") (pinfunction "RFU/~{RST}_3") (pintype "bidirectional"))
      (node (ref "U2") (pin "11") (pinfunction "VCC_11_11") (pintype "bidirectional"))
      (node (ref "U2") (pin "33") (pinfunction "VCC_33_33") (pintype "bidirectional"))
      (node (ref "U3") (pin "1") (pinfunction "VCC_1_1") (pintype "bidirectional"))
      (node (ref "U3") (pin "17") (pinfunction "VCC_17_17") (pintype "bidirectional"))
      (node (ref "U3") (pin "5") (pinfunction "VCCA_5") (pintype "bidirectional"))
      (node (ref "U5") (pin "1") (pinfunction "VCC_1_1") (pintype "bidirectional"))
      (node (ref "U5") (pin "17") (pinfunction "VCC_17_17") (pintype "bidirectional"))
      (node (ref "U5") (pin "5") (pinfunction "VCCA_5") (pintype "bidirectional"))
      (node (ref "U6") (pin "1") (pinfunction "VCC_1_1") (pintype "bidirectional"))
      (node (ref "U6") (pin "17") (pinfunction "VCC_17_17") (pintype "bidirectional"))
      (node (ref "U6") (pin "5") (pinfunction "VCCA_5") (pintype "bidirectional"))
      (node (ref "U7") (pin "1") (pinfunction "VCC_1_1") (pintype "bidirectional"))
      (node (ref "U7") (pin "17") (pinfunction "VCC_17_17") (pintype "bidirectional"))
      (node (ref "U7") (pin "5") (pinfunction "VCCA_5") (pintype "bidirectional"))
      (node (ref "U8") (pin "5") (pinfunction "VOUT_5") (pintype "bidirectional"))
      (node (ref "U9") (pin "1") (pinfunction "VCC_1_1") (pintype "bidirectional"))
      (node (ref "U9") (pin "17") (pinfunction "VCC_17_17") (pintype "bidirectional"))
      (node (ref "U9") (pin "5") (pinfunction "VCCA_5") (pintype "bidirectional"))
    )
    (net (code "121") (name "unconnected-(U1-VBAT-Pad6)") (class "Default")
      (node (ref "U1") (pin "6") (pinfunction "VBAT_6") (pintype "bidirectional"))
    )
    (net (code "122") (name "unconnected-(U8-NC-Pad4)") (class "Default")
      (node (ref "U8") (pin "4") (pinfunction "NC_4") (pintype "bidirectional"))
    )
    (net (code "123") (name "unconnected-(U10-DNU_4-Pad4)") (class "Default")
      (node (ref "U10") (pin "4") (pinfunction "DNU_4_4") (pintype "bidirectional"))
    )
    (net (code "124") (name "unconnected-(U10-DNU_5-Pad5)") (class "Default")
      (node (ref "U10") (pin "5") (pinfunction "DNU_5_5") (pintype "bidirectional"))
    )
    (net (code "125") (name "unconnected-(U10-DNU_11-Pad11)") (class "Default")
      (node (ref "U10") (pin "11") (pinfunction "DNU_11_11") (pintype "bidirectional"))
    )
    (net (code "126") (name "unconnected-(U10-DNU_12-Pad12)") (class "Default")
      (node (ref "U10") (pin "12") (pinfunction "DNU_12_12") (pintype "bidirectional"))
    )
    (net (code "127") (name "unconnected-(U10-IO2{slash}~{WP}-Pad9)") (class "Default")
      (node (ref "U10") (pin "9") (pinfunction "IO2/~{WP}_9") (pintype "bidirectional"))
    )
    (net (code "128") (name "unconnected-(U10-IO3{slash}~{HOLD}-Pad1)") (class "Default")
      (node (ref "U10") (pin "1") (pinfunction "IO3/~{HOLD}_1") (pintype "bidirectional"))
    )
    (net (code "129") (name "unconnected-(U10-NC-Pad13)") (class "Default")
      (node (ref "U10") (pin "13") (pinfunction "NC_13") (pintype "bidirectional"))
    )
    (net (code "130") (name "unconnected-(U10-RFU_6-Pad6)") (class "Default")
      (node (ref "U10") (pin "6") (pinfunction "RFU_6_6") (pintype "bidirectional"))
    )
  )
)
